# 2_PIS_TQ2416____V0_1.net
KiCad netlist of a schematic drawn in Altium Designer
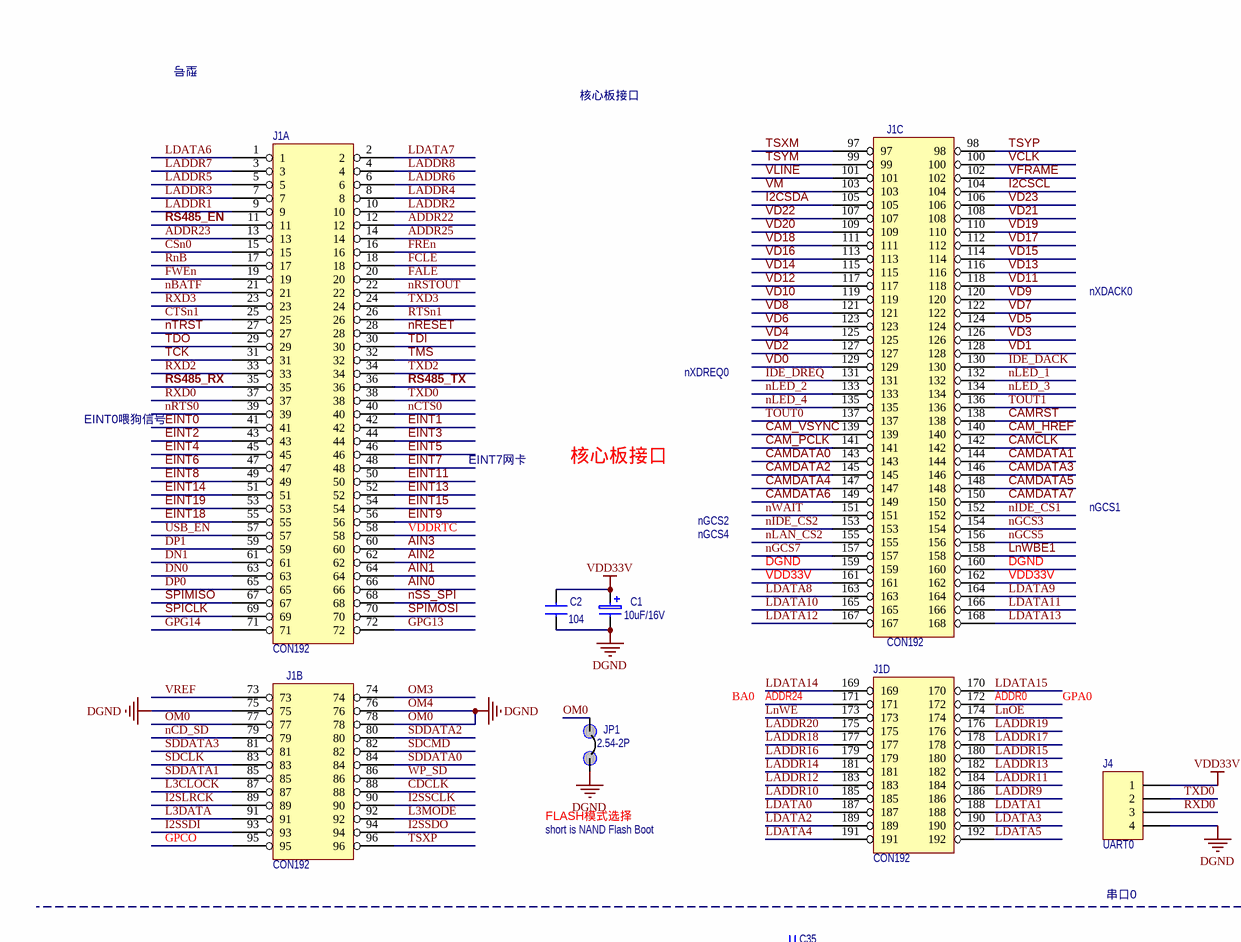
[diagram p0: 宁波2号线PIS_TQ2416底板_原理图_V0.1.schdoc, top left]
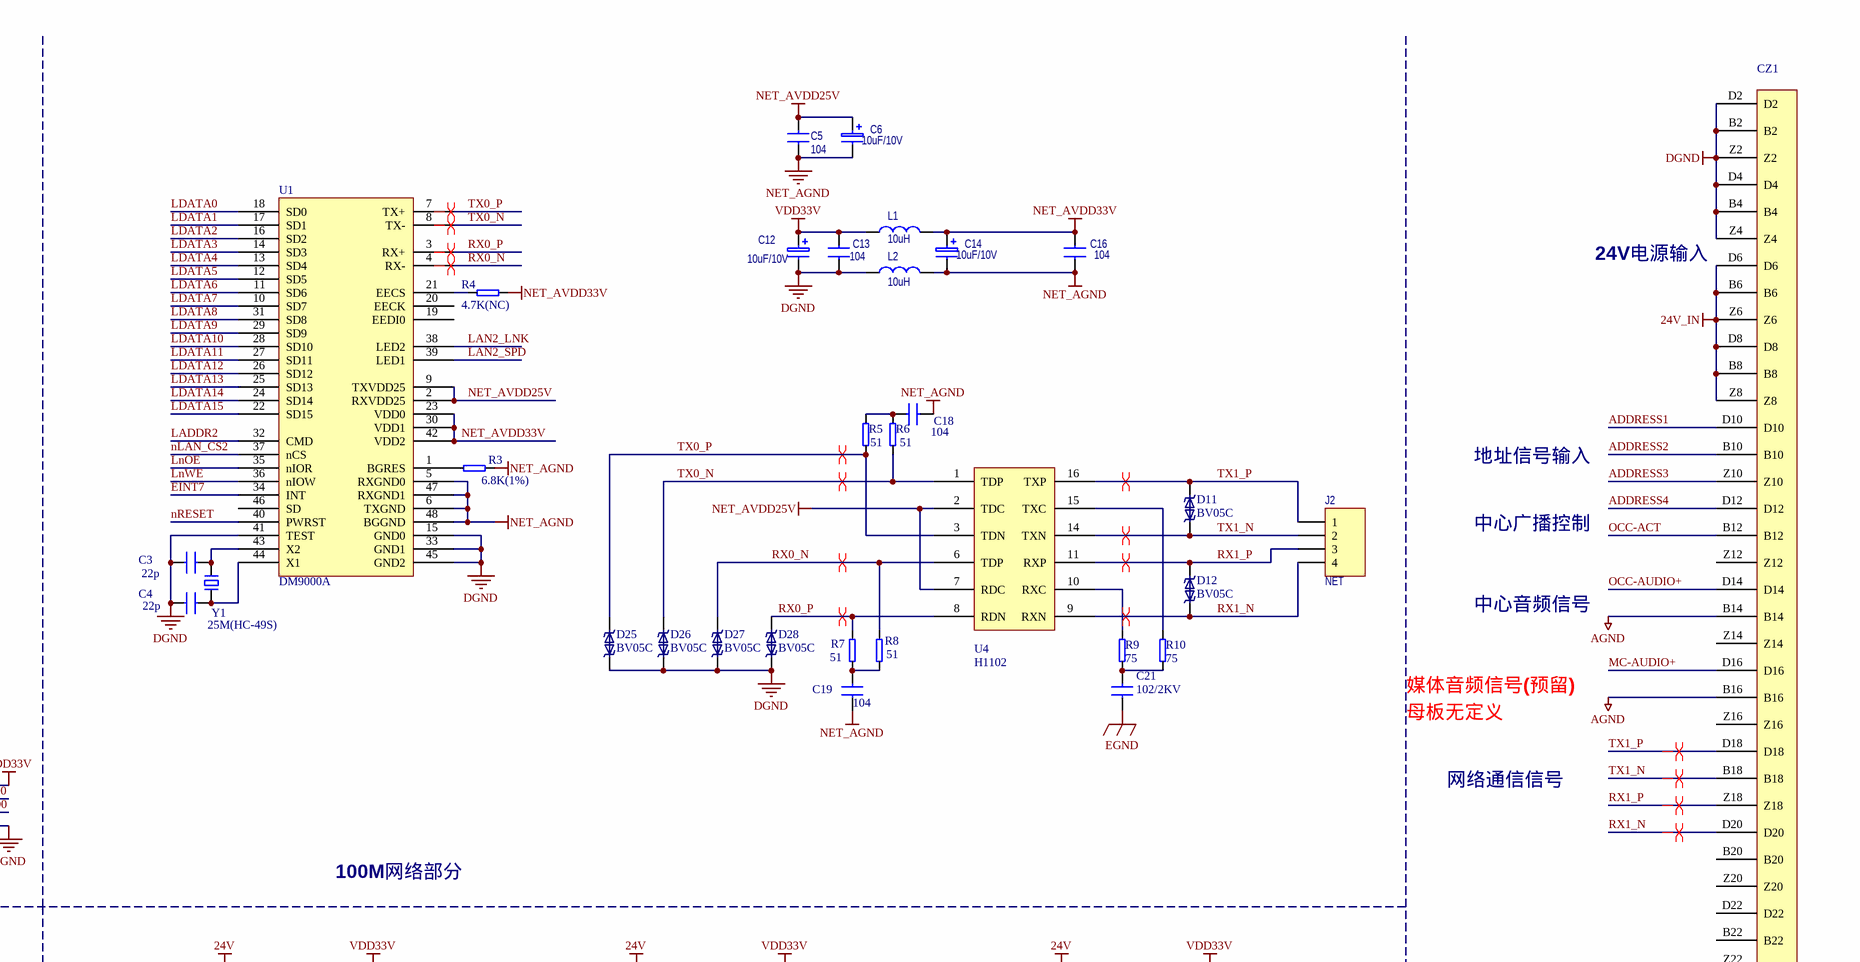
[diagram p1: 宁波2号线PIS_TQ2416底板_原理图_V0.1.schdoc, top right]
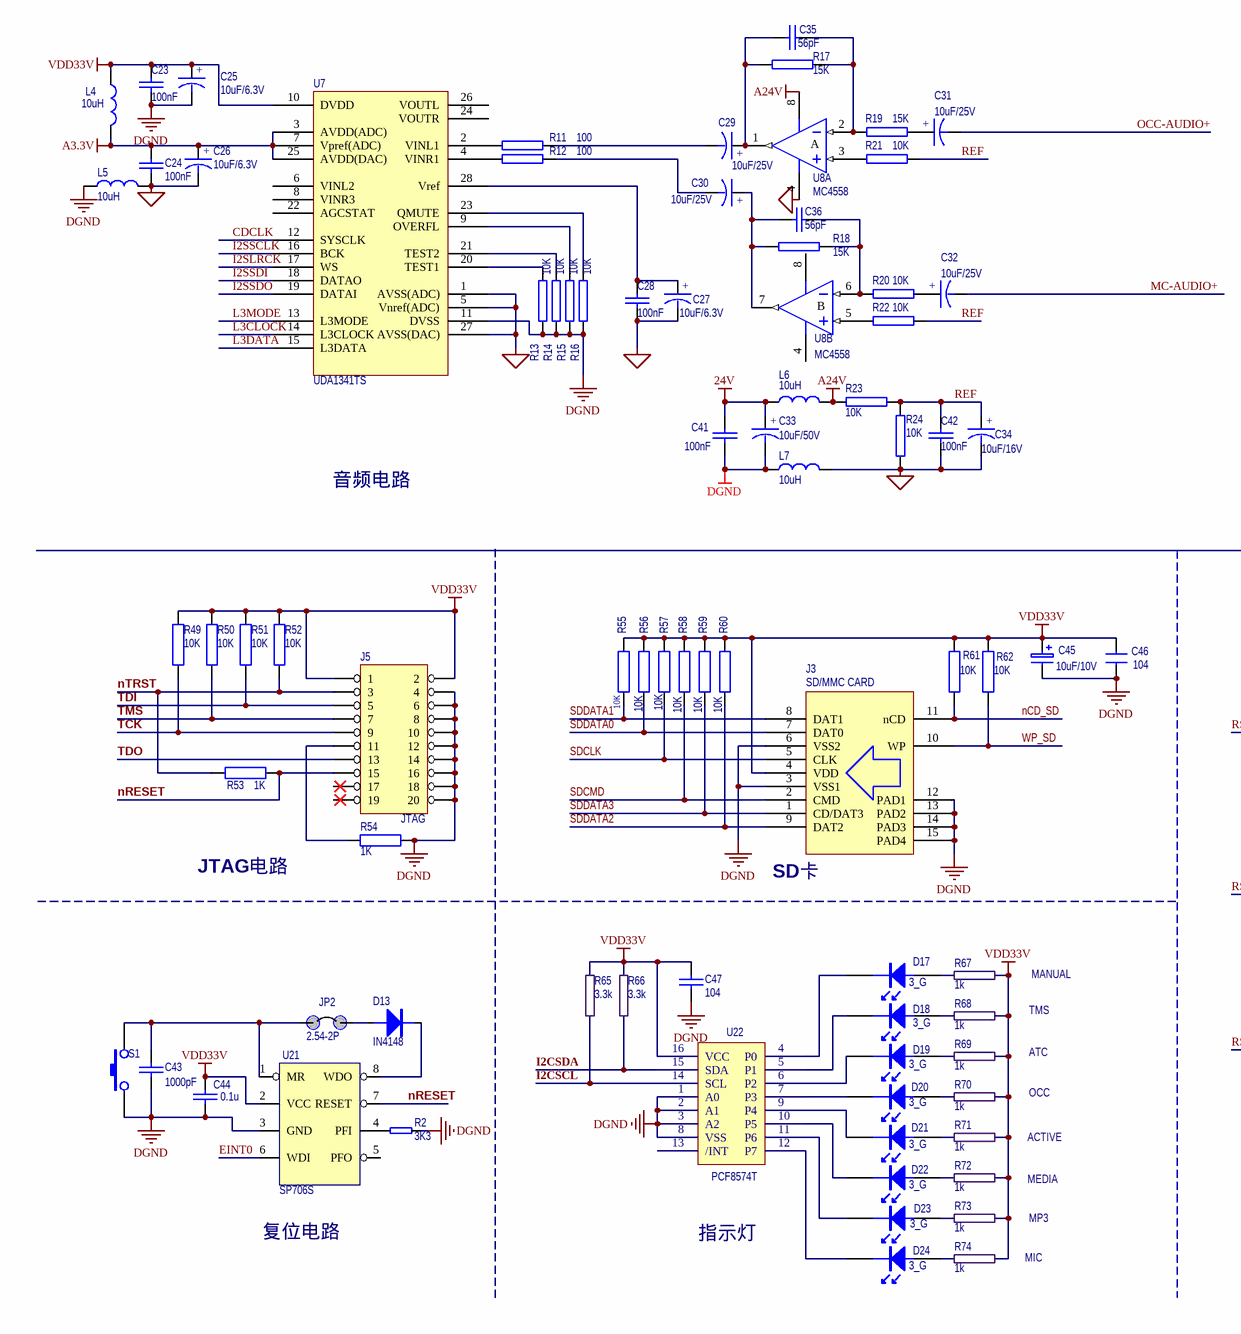
[diagram p2: 宁波2号线PIS_TQ2416底板_原理图_V0.1.schdoc, bottom left]
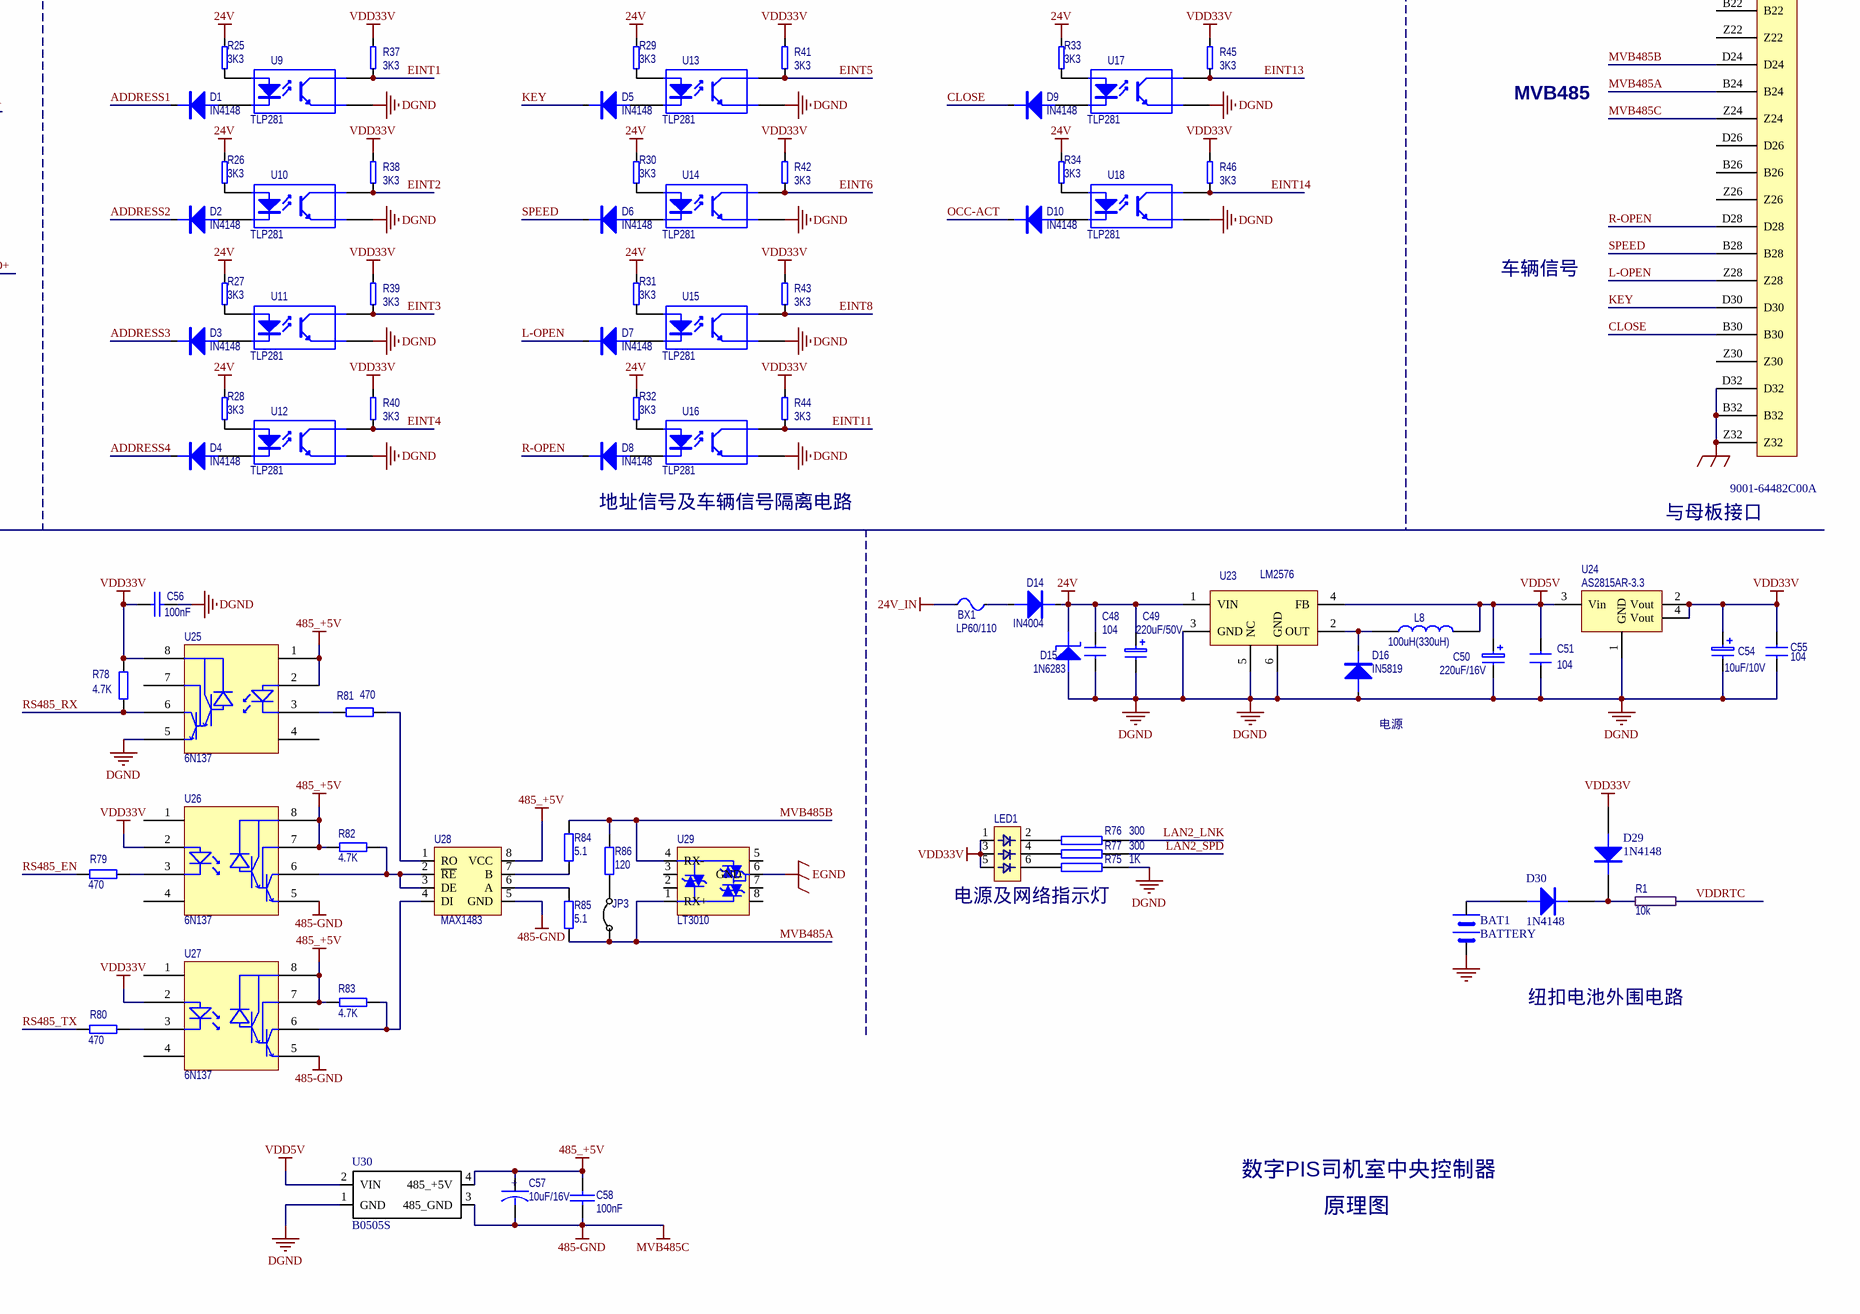
[diagram p3: 宁波2号线PIS_TQ2416底板_原理图_V0.1.schdoc, bottom right]

(export (version "E")
  (design (tool "Eeschema 10.0.6"))
  (components
    (comp (ref "BAT1") (value "BATTERY") (footprint "BAT600") (libsource (lib "*") (part "BATTERY")))
    (comp (ref "BX1") (value "LP60/110") (footprint "BX") (libsource (lib "*") (part "BX1")))
    (comp (ref "C1")
      (value "10uF/16V")
      (footprint "1206E")
      (description "Bi-Polar Capacitor")
      (fields (field (name "Comment") "10uF/10V"))
      (libsource (lib "*") (part "CAPBP2"))
    )
    (comp (ref "C2")
      (value "104")
      (footprint "0805C")
      (description "Capacitor")
      (libsource (lib "*") (part "CAP"))
    )
    (comp (ref "C3")
      (value "22p")
      (footprint "0805C")
      (description "Capacitor")
      (libsource (lib "*") (part "CAP"))
    )
    (comp (ref "C4")
      (value "22p")
      (footprint "0805C")
      (description "Capacitor")
      (libsource (lib "*") (part "CAP"))
    )
    (comp (ref "C5")
      (value "104")
      (footprint "0805C")
      (description "Capacitor")
      (libsource (lib "*") (part "CAP"))
    )
    (comp (ref "C6")
      (value "10uF/10V")
      (footprint "1206E")
      (description "Bi-Polar Capacitor")
      (libsource (lib "*") (part "CAPBP2"))
    )
    (comp (ref "C12")
      (value "10uF/10V")
      (footprint "1206E")
      (description "Bi-Polar Capacitor")
      (libsource (lib "*") (part "CAPBP2"))
    )
    (comp (ref "C13")
      (value "104")
      (footprint "0805C")
      (description "Capacitor")
      (libsource (lib "*") (part "CAP"))
    )
    (comp (ref "C14")
      (value "10uF/10V")
      (footprint "1206E")
      (description "Bi-Polar Capacitor")
      (libsource (lib "*") (part "CAPBP2"))
    )
    (comp (ref "C16")
      (value "104")
      (footprint "0805C")
      (description "Capacitor")
      (libsource (lib "*") (part "CAP"))
    )
    (comp (ref "C18")
      (value "104")
      (footprint "0805C")
      (description "Capacitor")
      (libsource (lib "*") (part "CAP"))
    )
    (comp (ref "C19")
      (value "104")
      (footprint "0805C")
      (description "Capacitor")
      (libsource (lib "*") (part "CAP"))
    )
    (comp (ref "C21")
      (value "102/2KV")
      (footprint "1206")
      (description "Capacitor")
      (libsource (lib "*") (part "CAP"))
    )
    (comp (ref "C23")
      (value "100nF")
      (footprint "0805C")
      (description "Capacitor")
      (libsource (lib "") (part "CAP_1"))
    )
    (comp (ref "C24")
      (value "100nF")
      (footprint "0805C")
      (description "Capacitor")
      (libsource (lib "") (part "CAP_1"))
    )
    (comp (ref "C25")
      (value "10uF/6.3V")
      (footprint "1206E")
      (description "Capacitor")
      (libsource (lib "*") (part "CAPACITOR POL"))
    )
    (comp (ref "C26")
      (value "10uF/6.3V")
      (footprint "1206E")
      (description "Capacitor")
      (libsource (lib "*") (part "CAPACITOR POL"))
    )
    (comp (ref "C27")
      (value "10uF/6.3V")
      (footprint "1206E")
      (description "Capacitor")
      (libsource (lib "*") (part "CAPACITOR POL"))
    )
    (comp (ref "C28")
      (value "100nF")
      (footprint "0805C")
      (description "Capacitor")
      (libsource (lib "") (part "CAP_1"))
    )
    (comp (ref "C29")
      (value "10uF/25V")
      (footprint "RB.1/.2")
      (description "Capacitor")
      (libsource (lib "*") (part "CAPACITOR POL"))
    )
    (comp (ref "C30")
      (value "10uF/25V")
      (footprint "RB.1/.2")
      (description "Capacitor")
      (libsource (lib "*") (part "CAPACITOR POL"))
    )
    (comp (ref "C31")
      (value "10uF/25V")
      (footprint "RB.1/.2")
      (description "Capacitor")
      (libsource (lib "*") (part "CAPACITOR POL"))
    )
    (comp (ref "C32")
      (value "10uF/25V")
      (footprint "RB.1/.2")
      (description "Capacitor")
      (libsource (lib "*") (part "CAPACITOR POL"))
    )
    (comp (ref "C33")
      (value "10uF/50V")
      (footprint "CAP-B")
      (description "Capacitor")
      (libsource (lib "*") (part "CAPACITOR POL"))
    )
    (comp (ref "C34")
      (value "10uF/16V")
      (footprint "CAP-B")
      (description "Capacitor")
      (libsource (lib "*") (part "CAPACITOR POL"))
    )
    (comp (ref "C35")
      (value "56pF")
      (footprint "0805C")
      (description "Capacitor")
      (libsource (lib "") (part "CAP_1"))
    )
    (comp (ref "C36")
      (value "56pF")
      (footprint "0805C")
      (description "Capacitor")
      (libsource (lib "") (part "CAP_1"))
    )
    (comp (ref "C41")
      (value "100nF")
      (footprint "0805C")
      (description "Capacitor")
      (libsource (lib "") (part "CAP_1"))
    )
    (comp (ref "C42")
      (value "100nF")
      (footprint "0805C")
      (description "Capacitor")
      (libsource (lib "") (part "CAP_1"))
    )
    (comp (ref "C43")
      (value "1000pF")
      (footprint "0805C")
      (description "Capacitor")
      (libsource (lib "") (part "CAP_2"))
    )
    (comp (ref "C44")
      (value "0.1u")
      (footprint "0805C")
      (description "Capacitor")
      (libsource (lib "") (part "CAP_2"))
    )
    (comp (ref "C45")
      (value "10uF/10V")
      (footprint "1206E")
      (description "Bi-Polar Capacitor")
      (libsource (lib "*") (part "CAPBP2"))
    )
    (comp (ref "C46")
      (value "104")
      (footprint "0805C")
      (description "Capacitor")
      (libsource (lib "*") (part "CAP"))
    )
    (comp (ref "C47")
      (value "104")
      (footprint "0805C")
      (description "Capacitor")
      (libsource (lib "") (part "CAP_3"))
    )
    (comp (ref "C48")
      (value "104")
      (footprint "0805C")
      (description "Capacitor")
      (libsource (lib "*") (part "CAP"))
    )
    (comp (ref "C49")
      (value "220uF/50V")
      (footprint "RB.2/.4")
      (description "Bi-Polar Capacitor")
      (libsource (lib "*") (part "CAPBP2"))
    )
    (comp (ref "C50")
      (value "220uF/16V")
      (footprint "RB.2/.4")
      (description "Bi-Polar Capacitor")
      (libsource (lib "*") (part "CAPBP2"))
    )
    (comp (ref "C51")
      (value "104")
      (footprint "0805C")
      (description "Capacitor")
      (libsource (lib "*") (part "CAP"))
    )
    (comp (ref "C54")
      (value "10uF/10V")
      (footprint "RB.2/.4")
      (description "Bi-Polar Capacitor")
      (fields (field (name "Comment") "220uF/16V"))
      (libsource (lib "*") (part "CAPBP2"))
    )
    (comp (ref "C55")
      (value "104")
      (footprint "0805C")
      (description "Capacitor")
      (libsource (lib "*") (part "CAP"))
    )
    (comp (ref "C56")
      (value "100nF")
      (footprint "0805C")
      (description "Capacitor")
      (libsource (lib "") (part "CAP_2"))
    )
    (comp (ref "C57")
      (value "10uF/16V")
      (footprint "1206E")
      (description "Capacitor")
      (libsource (lib "") (part "CAPACITOR POL_1"))
    )
    (comp (ref "C58")
      (value "100nF")
      (footprint "0805C")
      (description "Capacitor")
      (libsource (lib "") (part "CAP_1"))
    )
    (comp (ref "CZ1")
      (value "9001-64482C00A")
      (footprint "HARTING09061486901")
      (libsource (lib "*") (part "HARTING-48P"))
    )
    (comp (ref "D1")
      (value "IN4148")
      (footprint "SOD-323")
      (description "Diode")
      (libsource (lib "*") (part "DIODE"))
    )
    (comp (ref "D2")
      (value "IN4148")
      (footprint "SOD-323")
      (description "Diode")
      (libsource (lib "*") (part "DIODE"))
    )
    (comp (ref "D3")
      (value "IN4148")
      (footprint "SOD-323")
      (description "Diode")
      (libsource (lib "*") (part "DIODE"))
    )
    (comp (ref "D4")
      (value "IN4148")
      (footprint "SOD-323")
      (description "Diode")
      (libsource (lib "*") (part "DIODE"))
    )
    (comp (ref "D5")
      (value "IN4148")
      (footprint "SOD-323")
      (description "Diode")
      (libsource (lib "*") (part "DIODE"))
    )
    (comp (ref "D6")
      (value "IN4148")
      (footprint "SOD-323")
      (description "Diode")
      (libsource (lib "*") (part "DIODE"))
    )
    (comp (ref "D7")
      (value "IN4148")
      (footprint "SOD-323")
      (description "Diode")
      (libsource (lib "*") (part "DIODE"))
    )
    (comp (ref "D8")
      (value "IN4148")
      (footprint "SOD-323")
      (description "Diode")
      (libsource (lib "*") (part "DIODE"))
    )
    (comp (ref "D9")
      (value "IN4148")
      (footprint "SOD-323")
      (description "Diode")
      (libsource (lib "*") (part "DIODE"))
    )
    (comp (ref "D10")
      (value "IN4148")
      (footprint "SOD-323")
      (description "Diode")
      (libsource (lib "*") (part "DIODE"))
    )
    (comp (ref "D11") (value "BV05C") (footprint "SOD-323") (libsource (lib "Sch") (part "BV05C")))
    (comp (ref "D12") (value "BV05C") (footprint "SOD-323") (libsource (lib "Sch") (part "BV05C")))
    (comp (ref "D13")
      (value "IN4148")
      (footprint "0805AK")
      (description "Diode")
      (libsource (lib "*") (part "DIODE"))
    )
    (comp (ref "D14")
      (value "IN4004")
      (footprint "1206AK")
      (description "Diode")
      (libsource (lib "*") (part "DIODE"))
    )
    (comp (ref "D15")
      (value "1N6283")
      (footprint "DIODE0.5")
      (description "Zener Diode")
      (libsource (lib "*") (part "ZENER2"))
    )
    (comp (ref "D16")
      (value "IN5819")
      (footprint "1206AK")
      (description "Diode")
      (libsource (lib "*") (part "DIODE"))
    )
    (comp (ref "D17") (value "3_G") (footprint "LED-1") (libsource (lib "*") (part "LED")))
    (comp (ref "D18") (value "3_G") (footprint "LED-1") (libsource (lib "*") (part "LED")))
    (comp (ref "D19") (value "3_G") (footprint "LED-1") (libsource (lib "*") (part "LED")))
    (comp (ref "D20") (value "3_G") (footprint "LED-1") (libsource (lib "*") (part "LED")))
    (comp (ref "D21") (value "3_G") (footprint "LED-1") (libsource (lib "*") (part "LED")))
    (comp (ref "D22") (value "3_G") (footprint "LED-1") (libsource (lib "*") (part "LED")))
    (comp (ref "D23") (value "3_G") (footprint "LED-1") (libsource (lib "*") (part "LED")))
    (comp (ref "D24") (value "3_G") (footprint "LED-1") (libsource (lib "*") (part "LED")))
    (comp (ref "D25") (value "BV05C") (footprint "SOD-323") (libsource (lib "Sch") (part "BV05C")))
    (comp (ref "D26") (value "BV05C") (footprint "SOD-323") (libsource (lib "Sch") (part "BV05C")))
    (comp (ref "D27") (value "BV05C") (footprint "SOD-323") (libsource (lib "Sch") (part "BV05C")))
    (comp (ref "D28") (value "BV05C") (footprint "SOD-323") (libsource (lib "Sch") (part "BV05C")))
    (comp (ref "D29")
      (value "1N4148")
      (footprint "SOD-323")
      (description "Diode")
      (libsource (lib "") (part "DIODE_1"))
    )
    (comp (ref "D30")
      (value "1N4148")
      (footprint "SOD-323")
      (description "Diode")
      (libsource (lib "") (part "DIODE_1"))
    )
    (comp (ref "J1") (value "CON192") (footprint "CON192_2.0") (libsource (lib "*") (part "CON192")))
    (comp (ref "J2")
      (value "NET")
      (footprint "SIP-4")
      (description "Header, 4-Pin")
      (fields (field (name "PUBLISHER") "10K"))
      (libsource (lib "") (part "Header 4_1"))
    )
    (comp (ref "J3") (value "SD/MMC CARD") (footprint "SD_CARD(LONG)") (libsource (lib "*") (part "SD-CARD")))
    (comp (ref "J4")
      (value "UART0")
      (footprint "SIP-4")
      (description "Header, 4-Pin")
      (fields (field (name "PUBLISHER") "10K"))
      (libsource (lib "*") (part "Header 4"))
    )
    (comp (ref "J5") (value "JTAG") (footprint "DC3-20T") (libsource (lib "*") (part "HEADER 10X2")))
    (comp (ref "JP1") (value "2.54-2P") (footprint "JMP-2") (libsource (lib "*") (part "TX")))
    (comp (ref "JP2") (value "2.54-2P") (footprint "SIP-2") (libsource (lib "*") (part "TX")))
    (comp (ref "JP3") (value "~") (footprint "SIP-2") (libsource (lib "*") (part "J2")))
    (comp (ref "L1") (value "10uH") (footprint "1206") (libsource (lib "*") (part "INDUCTOR1")))
    (comp (ref "L2") (value "10uH") (footprint "1206") (libsource (lib "*") (part "INDUCTOR1")))
    (comp (ref "L4") (value "10uH") (footprint "1206") (libsource (lib "") (part "INDUCTOR1_2")))
    (comp (ref "L5") (value "10uH") (footprint "1206") (libsource (lib "*") (part "INDUCTOR1")))
    (comp (ref "L6") (value "10uH") (footprint "1206") (libsource (lib "*") (part "INDUCTOR1")))
    (comp (ref "L7") (value "10uH") (footprint "1206") (libsource (lib "*") (part "INDUCTOR1")))
    (comp (ref "L8") (value "100uH(330uH)") (footprint "DG300") (libsource (lib "") (part "INDUCTOR1_1")))
    (comp (ref "LED1") (value "~") (footprint "LED-3") (libsource (lib "*") (part "3-LED")))
    (comp (ref "R1") (value "10k") (footprint "0805R") (libsource (lib "") (part "R_1")))
    (comp (ref "R2") (value "3K3") (footprint "0805R") (libsource (lib "*") (part "R")))
    (comp (ref "R3") (value "6.8K(1%)") (footprint "0805R") (libsource (lib "") (part "R_2")))
    (comp (ref "R4") (value "4.7K(NC)") (footprint "0805R") (libsource (lib "") (part "R_2")))
    (comp (ref "R5") (value "51") (footprint "0805R") (libsource (lib "") (part "R_2")))
    (comp (ref "R6") (value "51") (footprint "0805R") (libsource (lib "") (part "R_2")))
    (comp (ref "R7") (value "51") (footprint "0805R") (libsource (lib "") (part "R_2")))
    (comp (ref "R8") (value "51") (footprint "0805R") (libsource (lib "") (part "R_2")))
    (comp (ref "R9") (value "75") (footprint "0805R") (libsource (lib "") (part "R_2")))
    (comp (ref "R10") (value "75") (footprint "0805R") (libsource (lib "") (part "R_2")))
    (comp (ref "R11") (value "100") (footprint "0805R") (libsource (lib "") (part "RES2_4")))
    (comp (ref "R12") (value "100") (footprint "0805R") (libsource (lib "") (part "RES2_4")))
    (comp (ref "R13") (value "10K") (footprint "0805R") (libsource (lib "") (part "RES2_4")))
    (comp (ref "R14") (value "10K") (footprint "0805R") (libsource (lib "") (part "RES2_4")))
    (comp (ref "R15") (value "10K") (footprint "0805R") (libsource (lib "") (part "RES2_4")))
    (comp (ref "R16") (value "10K") (footprint "0805R") (libsource (lib "") (part "RES2_4")))
    (comp (ref "R17") (value "15K") (footprint "0805R") (libsource (lib "") (part "RES2_4")))
    (comp (ref "R18") (value "15K") (footprint "0805R") (libsource (lib "") (part "RES2_4")))
    (comp (ref "R19") (value "15K") (footprint "0805R") (libsource (lib "") (part "RES2_4")))
    (comp (ref "R20") (value "10K") (footprint "0805R") (libsource (lib "") (part "RES2_4")))
    (comp (ref "R21") (value "10K") (footprint "0805R") (libsource (lib "") (part "RES2_4")))
    (comp (ref "R22") (value "10K") (footprint "0805R") (libsource (lib "") (part "RES2_4")))
    (comp (ref "R23") (value "10K") (footprint "0805R") (libsource (lib "") (part "RES2_4")))
    (comp (ref "R24") (value "10K") (footprint "0805R") (libsource (lib "") (part "RES2_4")))
    (comp (ref "R25") (value "3K3") (footprint "0805R") (libsource (lib "*") (part "R")))
    (comp (ref "R26") (value "3K3") (footprint "0805R") (libsource (lib "*") (part "R")))
    (comp (ref "R27") (value "3K3") (footprint "0805R") (libsource (lib "*") (part "R")))
    (comp (ref "R28") (value "3K3") (footprint "0805R") (libsource (lib "*") (part "R")))
    (comp (ref "R29") (value "3K3") (footprint "0805R") (libsource (lib "*") (part "R")))
    (comp (ref "R30") (value "3K3") (footprint "0805R") (libsource (lib "*") (part "R")))
    (comp (ref "R31") (value "3K3") (footprint "0805R") (libsource (lib "*") (part "R")))
    (comp (ref "R32") (value "3K3") (footprint "0805R") (libsource (lib "*") (part "R")))
    (comp (ref "R33") (value "3K3") (footprint "0805R") (libsource (lib "*") (part "R")))
    (comp (ref "R34") (value "3K3") (footprint "0805R") (libsource (lib "*") (part "R")))
    (comp (ref "R37") (value "3K3") (footprint "0805R") (libsource (lib "*") (part "R")))
    (comp (ref "R38") (value "3K3") (footprint "0805R") (libsource (lib "*") (part "R")))
    (comp (ref "R39") (value "3K3") (footprint "0805R") (libsource (lib "*") (part "R")))
    (comp (ref "R40") (value "3K3") (footprint "0805R") (libsource (lib "*") (part "R")))
    (comp (ref "R41") (value "3K3") (footprint "0805R") (libsource (lib "*") (part "R")))
    (comp (ref "R42") (value "3K3") (footprint "0805R") (libsource (lib "*") (part "R")))
    (comp (ref "R43") (value "3K3") (footprint "0805R") (libsource (lib "*") (part "R")))
    (comp (ref "R44") (value "3K3") (footprint "0805R") (libsource (lib "*") (part "R")))
    (comp (ref "R45") (value "3K3") (footprint "0805R") (libsource (lib "*") (part "R")))
    (comp (ref "R46") (value "3K3") (footprint "0805R") (libsource (lib "*") (part "R")))
    (comp (ref "R49")
      (value "10K")
      (footprint "0805R")
      (description "Resistor")
      (libsource (lib "") (part "RES2_1"))
    )
    (comp (ref "R50")
      (value "10K")
      (footprint "0805R")
      (description "Resistor")
      (libsource (lib "") (part "RES2_1"))
    )
    (comp (ref "R51")
      (value "10K")
      (footprint "0805R")
      (description "Resistor")
      (libsource (lib "") (part "RES2_1"))
    )
    (comp (ref "R52")
      (value "10K")
      (footprint "0805R")
      (description "Resistor")
      (libsource (lib "") (part "RES2_1"))
    )
    (comp (ref "R53")
      (value "1K")
      (footprint "0805R")
      (description "Resistor")
      (libsource (lib "") (part "RES2_3"))
    )
    (comp (ref "R54")
      (value "1K")
      (footprint "0805R")
      (description "Resistor")
      (libsource (lib "") (part "RES2_3"))
    )
    (comp (ref "R55")
      (value "10K")
      (footprint "0805R")
      (description "Resistor")
      (libsource (lib "") (part "RES2_1"))
    )
    (comp (ref "R56")
      (value "10K")
      (footprint "0805R")
      (description "Resistor")
      (libsource (lib "") (part "RES2_1"))
    )
    (comp (ref "R57")
      (value "10K")
      (footprint "0805R")
      (description "Resistor")
      (libsource (lib "") (part "RES2_1"))
    )
    (comp (ref "R58")
      (value "10K")
      (footprint "0805R")
      (description "Resistor")
      (libsource (lib "") (part "RES2_1"))
    )
    (comp (ref "R59")
      (value "10K")
      (footprint "0805R")
      (description "Resistor")
      (libsource (lib "") (part "RES2_1"))
    )
    (comp (ref "R60")
      (value "10K")
      (footprint "0805R")
      (description "Resistor")
      (libsource (lib "") (part "RES2_1"))
    )
    (comp (ref "R61")
      (value "10K")
      (footprint "0805R")
      (description "Resistor")
      (libsource (lib "") (part "RES2_1"))
    )
    (comp (ref "R62")
      (value "10K")
      (footprint "0805R")
      (description "Resistor")
      (libsource (lib "") (part "RES2_1"))
    )
    (comp (ref "R65") (value "3.3k") (footprint "0805R") (libsource (lib "") (part "R_1")))
    (comp (ref "R66") (value "3.3k") (footprint "0805R") (libsource (lib "") (part "R_1")))
    (comp (ref "R67") (value "1k") (footprint "0805R") (libsource (lib "") (part "R_1")))
    (comp (ref "R68") (value "1k") (footprint "0805R") (libsource (lib "") (part "R_1")))
    (comp (ref "R69") (value "1k") (footprint "0805R") (libsource (lib "") (part "R_1")))
    (comp (ref "R70") (value "1k") (footprint "0805R") (libsource (lib "") (part "R_1")))
    (comp (ref "R71") (value "1k") (footprint "0805R") (libsource (lib "") (part "R_1")))
    (comp (ref "R72") (value "1k") (footprint "0805R") (libsource (lib "") (part "R_1")))
    (comp (ref "R73") (value "1k") (footprint "0805R") (libsource (lib "") (part "R_1")))
    (comp (ref "R74") (value "1k") (footprint "0805R") (libsource (lib "") (part "R_1")))
    (comp (ref "R75") (value "1K") (footprint "0805R") (libsource (lib "") (part "RES2_2")))
    (comp (ref "R76") (value "300") (footprint "0805R") (libsource (lib "") (part "RES2_2")))
    (comp (ref "R77") (value "300") (footprint "0805R") (libsource (lib "") (part "RES2_2")))
    (comp (ref "R78") (value "4.7K") (footprint "0805R") (libsource (lib "*") (part "RES2")))
    (comp (ref "R79") (value "470") (footprint "0805R") (libsource (lib "*") (part "RES2")))
    (comp (ref "R80") (value "470") (footprint "0805R") (libsource (lib "*") (part "RES2")))
    (comp (ref "R81") (value "470") (footprint "0805R") (libsource (lib "*") (part "RES2")))
    (comp (ref "R82") (value "4.7K") (footprint "0805R") (libsource (lib "*") (part "RES2")))
    (comp (ref "R83") (value "4.7K") (footprint "0805R") (libsource (lib "*") (part "RES2")))
    (comp (ref "R84") (value "5.1") (footprint "0805R") (libsource (lib "*") (part "RES2")))
    (comp (ref "R85") (value "5.1") (footprint "0805R") (libsource (lib "*") (part "RES2")))
    (comp (ref "R86") (value "120") (footprint "0805R") (libsource (lib "*") (part "RES2")))
    (comp (ref "S1") (value "~") (footprint "KEY-6A") (libsource (lib "*") (part "SW-PB")))
    (comp (ref "U1") (value "DM9000A") (footprint "LQFP-48") (libsource (lib "*") (part "DM9000A")))
    (comp (ref "U4") (value "H1102") (footprint "SOP-16(Wide)") (libsource (lib "*") (part "H1102")))
    (comp (ref "U7") (value "UDA1341TS") (footprint "TSSOP-28") (libsource (lib "*") (part "UDA1341TS")))
    (comp (ref "U8")
      (value "MC4558")
      (footprint "SOP-8")
      (description "Dual Rail-to-Rail Operational Amplifier")
      (fields (field (name "PUBLISHER") "10K"))
      (libsource (lib "*") (part "OP295GS"))
    )
    (comp (ref "U9")
      (value "TLP281")
      (footprint "SOP-4")
      (description "Optoisolator")
      (libsource (lib "*") (part "OPTOISO1"))
    )
    (comp (ref "U10")
      (value "TLP281")
      (footprint "SOP-4")
      (description "Optoisolator")
      (libsource (lib "*") (part "OPTOISO1"))
    )
    (comp (ref "U11")
      (value "TLP281")
      (footprint "SOP-4")
      (description "Optoisolator")
      (libsource (lib "*") (part "OPTOISO1"))
    )
    (comp (ref "U12")
      (value "TLP281")
      (footprint "SOP-4")
      (description "Optoisolator")
      (libsource (lib "*") (part "OPTOISO1"))
    )
    (comp (ref "U13")
      (value "TLP281")
      (footprint "SOP-4")
      (description "Optoisolator")
      (libsource (lib "*") (part "OPTOISO1"))
    )
    (comp (ref "U14")
      (value "TLP281")
      (footprint "SOP-4")
      (description "Optoisolator")
      (libsource (lib "*") (part "OPTOISO1"))
    )
    (comp (ref "U15")
      (value "TLP281")
      (footprint "SOP-4")
      (description "Optoisolator")
      (libsource (lib "*") (part "OPTOISO1"))
    )
    (comp (ref "U16")
      (value "TLP281")
      (footprint "SOP-4")
      (description "Optoisolator")
      (libsource (lib "*") (part "OPTOISO1"))
    )
    (comp (ref "U17")
      (value "TLP281")
      (footprint "SOP-4")
      (description "Optoisolator")
      (libsource (lib "*") (part "OPTOISO1"))
    )
    (comp (ref "U18")
      (value "TLP281")
      (footprint "SOP-4")
      (description "Optoisolator")
      (libsource (lib "*") (part "OPTOISO1"))
    )
    (comp (ref "U21") (value "SP706S") (footprint "SOP-8") (libsource (lib "*") (part "MAX706R")))
    (comp (ref "U22") (value "PCF8574T") (footprint "SOP-16") (libsource (lib "*") (part "PCF8574")))
    (comp (ref "U23") (value "LM2576") (footprint "LM2576") (libsource (lib "*") (part "LM2576")))
    (comp (ref "U24") (value "AS2815AR-3.3") (footprint "TO-252") (libsource (lib "*") (part "LT1085")))
    (comp (ref "U25") (value "6N137") (footprint "SOP-8-2.54") (libsource (lib "") (part "6N138_1")))
    (comp (ref "U26") (value "6N137") (footprint "SOP-8-2.54") (libsource (lib "*") (part "6N138")))
    (comp (ref "U27") (value "6N137") (footprint "SOP-8-2.54") (libsource (lib "*") (part "6N138")))
    (comp (ref "U28") (value "MAX1483") (footprint "SOP-8") (libsource (lib "*") (part "MAX1483")))
    (comp (ref "U29") (value "LT3010") (footprint "SOP-8") (libsource (lib "*") (part "LT3010")))
    (comp (ref "U30") (value "B0505S") (footprint "B0505S") (libsource (lib "Sch") (part "B0505S")))
    (comp (ref "Y1") (value "25M(HC-49S)") (footprint "CRYSTAL") (libsource (lib "*") (part "JT")))
  )
  (nets
    (net (code "1") (name "/ADDR22") (class "Default")
      (node (ref "J1") (pin "12") (pinfunction "12_12") (pintype "passive"))
    )
    (net (code "2") (name "/ADDR23") (class "Default")
      (node (ref "J1") (pin "13") (pinfunction "13_13") (pintype "passive"))
    )
    (net (code "3") (name "/ADDR25") (class "Default")
      (node (ref "J1") (pin "14") (pinfunction "14_14") (pintype "passive"))
    )
    (net (code "4") (name "/ADDRESS1") (class "Default")
      (node (ref "CZ1") (pin "D10") (pinfunction "D10_D10") (pintype "passive"))
      (node (ref "D1") (pin "K") (pinfunction "K_K") (pintype "passive"))
    )
    (net (code "5") (name "/ADDRESS2") (class "Default")
      (node (ref "CZ1") (pin "B10") (pinfunction "B10_B10") (pintype "passive"))
      (node (ref "D2") (pin "K") (pinfunction "K_K") (pintype "passive"))
    )
    (net (code "6") (name "/ADDRESS3") (class "Default")
      (node (ref "CZ1") (pin "Z10") (pinfunction "Z10_Z10") (pintype "passive"))
      (node (ref "D3") (pin "K") (pinfunction "K_K") (pintype "passive"))
    )
    (net (code "7") (name "/ADDRESS4") (class "Default")
      (node (ref "CZ1") (pin "D12") (pinfunction "D12_D12") (pintype "passive"))
      (node (ref "D4") (pin "K") (pinfunction "K_K") (pintype "passive"))
    )
    (net (code "8") (name "/AIN0") (class "Default")
      (node (ref "J1") (pin "66") (pinfunction "66_66") (pintype "passive"))
    )
    (net (code "9") (name "/AIN1") (class "Default")
      (node (ref "J1") (pin "64") (pinfunction "64_64") (pintype "passive"))
    )
    (net (code "10") (name "/AIN2") (class "Default")
      (node (ref "J1") (pin "62") (pinfunction "62_62") (pintype "passive"))
    )
    (net (code "11") (name "/AIN3") (class "Default")
      (node (ref "J1") (pin "60") (pinfunction "60_60") (pintype "passive"))
    )
    (net (code "12") (name "/CAMCLK") (class "Default")
      (node (ref "J1") (pin "142") (pinfunction "142_142") (pintype "passive"))
    )
    (net (code "13") (name "/CAMDATA0") (class "Default")
      (node (ref "J1") (pin "143") (pinfunction "143_143") (pintype "passive"))
    )
    (net (code "14") (name "/CAMDATA1") (class "Default")
      (node (ref "J1") (pin "144") (pinfunction "144_144") (pintype "passive"))
    )
    (net (code "15") (name "/CAMDATA2") (class "Default")
      (node (ref "J1") (pin "145") (pinfunction "145_145") (pintype "passive"))
    )
    (net (code "16") (name "/CAMDATA3") (class "Default")
      (node (ref "J1") (pin "146") (pinfunction "146_146") (pintype "passive"))
    )
    (net (code "17") (name "/CAMDATA4") (class "Default")
      (node (ref "J1") (pin "147") (pinfunction "147_147") (pintype "passive"))
    )
    (net (code "18") (name "/CAMDATA5") (class "Default")
      (node (ref "J1") (pin "148") (pinfunction "148_148") (pintype "passive"))
    )
    (net (code "19") (name "/CAMDATA6") (class "Default")
      (node (ref "J1") (pin "149") (pinfunction "149_149") (pintype "passive"))
    )
    (net (code "20") (name "/CAMDATA7") (class "Default")
      (node (ref "J1") (pin "150") (pinfunction "150_150") (pintype "passive"))
    )
    (net (code "21") (name "/CAMRST") (class "Default")
      (node (ref "J1") (pin "138") (pinfunction "138_138") (pintype "passive"))
    )
    (net (code "22") (name "/CAM_HREF") (class "Default")
      (node (ref "J1") (pin "140") (pinfunction "140_140") (pintype "passive"))
    )
    (net (code "23") (name "/CAM_PCLK") (class "Default")
      (node (ref "J1") (pin "141") (pinfunction "141_141") (pintype "passive"))
    )
    (net (code "24") (name "/CAM_VSYNC") (class "Default")
      (node (ref "J1") (pin "139") (pinfunction "139_139") (pintype "passive"))
    )
    (net (code "25") (name "/CDCLK") (class "Default")
      (node (ref "J1") (pin "88") (pinfunction "88_88") (pintype "passive"))
      (node (ref "U7") (pin "12") (pinfunction "SYSCLK_12") (pintype "passive"))
    )
    (net (code "26") (name "/CLOSE") (class "Default")
      (node (ref "CZ1") (pin "B30") (pinfunction "B30_B30") (pintype "passive"))
      (node (ref "D9") (pin "K") (pinfunction "K_K") (pintype "passive"))
    )
    (net (code "27") (name "/CSn0") (class "Default")
      (node (ref "J1") (pin "15") (pinfunction "15_15") (pintype "passive"))
    )
    (net (code "28") (name "/CTSn1") (class "Default")
      (node (ref "J1") (pin "25") (pinfunction "25_25") (pintype "passive"))
    )
    (net (code "29") (name "/DN0") (class "Default")
      (node (ref "J1") (pin "63") (pinfunction "63_63") (pintype "passive"))
    )
    (net (code "30") (name "/DN1") (class "Default")
      (node (ref "J1") (pin "61") (pinfunction "61_61") (pintype "passive"))
    )
    (net (code "31") (name "/DP0") (class "Default")
      (node (ref "J1") (pin "65") (pinfunction "65_65") (pintype "passive"))
    )
    (net (code "32") (name "/DP1") (class "Default")
      (node (ref "J1") (pin "59") (pinfunction "59_59") (pintype "passive"))
    )
    (net (code "33") (name "/EINT0") (class "Default")
      (node (ref "J1") (pin "41") (pinfunction "41_41") (pintype "passive"))
      (node (ref "U21") (pin "6") (pinfunction "WDI_6") (pintype "passive"))
    )
    (net (code "34") (name "/EINT1") (class "Default")
      (node (ref "J1") (pin "42") (pinfunction "42_42") (pintype "passive"))
      (node (ref "R37") (pin "1") (pinfunction "1_1") (pintype "passive"))
      (node (ref "U9") (pin "4") (pinfunction "C_4") (pintype "passive"))
    )
    (net (code "35") (name "/EINT2") (class "Default")
      (node (ref "J1") (pin "43") (pinfunction "43_43") (pintype "passive"))
      (node (ref "R38") (pin "1") (pinfunction "1_1") (pintype "passive"))
      (node (ref "U10") (pin "4") (pinfunction "C_4") (pintype "passive"))
    )
    (net (code "36") (name "/EINT3") (class "Default")
      (node (ref "J1") (pin "44") (pinfunction "44_44") (pintype "passive"))
      (node (ref "R39") (pin "1") (pinfunction "1_1") (pintype "passive"))
      (node (ref "U11") (pin "4") (pinfunction "C_4") (pintype "passive"))
    )
    (net (code "37") (name "/EINT4") (class "Default")
      (node (ref "J1") (pin "45") (pinfunction "45_45") (pintype "passive"))
      (node (ref "R40") (pin "1") (pinfunction "1_1") (pintype "passive"))
      (node (ref "U12") (pin "4") (pinfunction "C_4") (pintype "passive"))
    )
    (net (code "38") (name "/EINT5") (class "Default")
      (node (ref "J1") (pin "46") (pinfunction "46_46") (pintype "passive"))
      (node (ref "R41") (pin "1") (pinfunction "1_1") (pintype "passive"))
      (node (ref "U13") (pin "4") (pinfunction "C_4") (pintype "passive"))
    )
    (net (code "39") (name "/EINT6") (class "Default")
      (node (ref "J1") (pin "47") (pinfunction "47_47") (pintype "passive"))
      (node (ref "R42") (pin "1") (pinfunction "1_1") (pintype "passive"))
      (node (ref "U14") (pin "4") (pinfunction "C_4") (pintype "passive"))
    )
    (net (code "40") (name "/EINT7") (class "Default")
      (node (ref "J1") (pin "48") (pinfunction "48_48") (pintype "passive"))
      (node (ref "U1") (pin "34") (pinfunction "INT_34") (pintype "passive"))
    )
    (net (code "41") (name "/EINT8") (class "Default")
      (node (ref "J1") (pin "49") (pinfunction "49_49") (pintype "passive"))
      (node (ref "R43") (pin "1") (pinfunction "1_1") (pintype "passive"))
      (node (ref "U15") (pin "4") (pinfunction "C_4") (pintype "passive"))
    )
    (net (code "42") (name "/EINT9") (class "Default")
      (node (ref "J1") (pin "56") (pinfunction "56_56") (pintype "passive"))
    )
    (net (code "43") (name "/EINT11") (class "Default")
      (node (ref "J1") (pin "50") (pinfunction "50_50") (pintype "passive"))
      (node (ref "R44") (pin "1") (pinfunction "1_1") (pintype "passive"))
      (node (ref "U16") (pin "4") (pinfunction "C_4") (pintype "passive"))
    )
    (net (code "44") (name "/EINT13") (class "Default")
      (node (ref "J1") (pin "52") (pinfunction "52_52") (pintype "passive"))
      (node (ref "R45") (pin "1") (pinfunction "1_1") (pintype "passive"))
      (node (ref "U17") (pin "4") (pinfunction "C_4") (pintype "passive"))
    )
    (net (code "45") (name "/EINT14") (class "Default")
      (node (ref "J1") (pin "51") (pinfunction "51_51") (pintype "passive"))
      (node (ref "R46") (pin "1") (pinfunction "1_1") (pintype "passive"))
      (node (ref "U18") (pin "4") (pinfunction "C_4") (pintype "passive"))
    )
    (net (code "46") (name "/EINT15") (class "Default")
      (node (ref "J1") (pin "54") (pinfunction "54_54") (pintype "passive"))
    )
    (net (code "47") (name "/EINT18") (class "Default")
      (node (ref "J1") (pin "55") (pinfunction "55_55") (pintype "passive"))
    )
    (net (code "48") (name "/EINT19") (class "Default")
      (node (ref "J1") (pin "53") (pinfunction "53_53") (pintype "passive"))
    )
    (net (code "49") (name "/FALE") (class "Default")
      (node (ref "J1") (pin "20") (pinfunction "20_20") (pintype "passive"))
    )
    (net (code "50") (name "/FCLE") (class "Default")
      (node (ref "J1") (pin "18") (pinfunction "18_18") (pintype "passive"))
    )
    (net (code "51") (name "/FREn") (class "Default")
      (node (ref "J1") (pin "16") (pinfunction "16_16") (pintype "passive"))
    )
    (net (code "52") (name "/FWEn") (class "Default")
      (node (ref "J1") (pin "19") (pinfunction "19_19") (pintype "passive"))
    )
    (net (code "53") (name "/GPCO") (class "Default")
      (node (ref "J1") (pin "95") (pinfunction "95_95") (pintype "passive"))
    )
    (net (code "54") (name "/GPG13") (class "Default")
      (node (ref "J1") (pin "72") (pinfunction "72_72") (pintype "passive"))
    )
    (net (code "55") (name "/GPG14") (class "Default")
      (node (ref "J1") (pin "71") (pinfunction "71_71") (pintype "passive"))
    )
    (net (code "56") (name "/I2CSCL") (class "Default")
      (node (ref "J1") (pin "104") (pinfunction "104_104") (pintype "passive"))
      (node (ref "R65") (pin "2") (pintype "passive"))
      (node (ref "U22") (pin "14") (pinfunction "SCL_14") (pintype "passive"))
    )
    (net (code "57") (name "/I2CSDA") (class "Default")
      (node (ref "J1") (pin "105") (pinfunction "105_105") (pintype "passive"))
      (node (ref "R66") (pin "2") (pintype "passive"))
      (node (ref "U22") (pin "15") (pinfunction "SDA_15") (pintype "passive"))
    )
    (net (code "58") (name "/I2SLRCK") (class "Default")
      (node (ref "J1") (pin "89") (pinfunction "89_89") (pintype "passive"))
      (node (ref "U7") (pin "17") (pinfunction "WS_17") (pintype "passive"))
    )
    (net (code "59") (name "/I2SSCLK") (class "Default")
      (node (ref "J1") (pin "90") (pinfunction "90_90") (pintype "passive"))
      (node (ref "U7") (pin "16") (pinfunction "BCK_16") (pintype "passive"))
    )
    (net (code "60") (name "/I2SSDI") (class "Default")
      (node (ref "J1") (pin "93") (pinfunction "93_93") (pintype "passive"))
      (node (ref "U7") (pin "18") (pinfunction "DATAO_18") (pintype "passive"))
    )
    (net (code "61") (name "/I2SSDO") (class "Default")
      (node (ref "J1") (pin "94") (pinfunction "94_94") (pintype "passive"))
      (node (ref "U7") (pin "19") (pinfunction "DATAI_19") (pintype "passive"))
    )
    (net (code "62") (name "/IDE_DACK") (class "Default")
      (node (ref "J1") (pin "130") (pinfunction "130_130") (pintype "passive"))
    )
    (net (code "63") (name "/IDE_DREQ") (class "Default")
      (node (ref "J1") (pin "131") (pinfunction "131_131") (pintype "passive"))
    )
    (net (code "64") (name "/KEY") (class "Default")
      (node (ref "CZ1") (pin "D30") (pinfunction "D30_D30") (pintype "passive"))
      (node (ref "D5") (pin "K") (pinfunction "K_K") (pintype "passive"))
    )
    (net (code "65") (name "/L-OPEN") (class "Default")
      (node (ref "CZ1") (pin "Z28") (pinfunction "Z28_Z28") (pintype "passive"))
      (node (ref "D7") (pin "K") (pinfunction "K_K") (pintype "passive"))
    )
    (net (code "66") (name "/L3CLOCK") (class "Default")
      (node (ref "J1") (pin "87") (pinfunction "87_87") (pintype "passive"))
      (node (ref "U7") (pin "14") (pinfunction "L3CLOCK_14") (pintype "passive"))
    )
    (net (code "67") (name "/L3DATA") (class "Default")
      (node (ref "J1") (pin "91") (pinfunction "91_91") (pintype "passive"))
      (node (ref "U7") (pin "15") (pinfunction "L3DATA_15") (pintype "passive"))
    )
    (net (code "68") (name "/L3MODE") (class "Default")
      (node (ref "J1") (pin "92") (pinfunction "92_92") (pintype "passive"))
      (node (ref "U7") (pin "13") (pinfunction "L3MODE_13") (pintype "passive"))
    )
    (net (code "69") (name "/LADDR1") (class "Default")
      (node (ref "J1") (pin "9") (pinfunction "9_9") (pintype "passive"))
    )
    (net (code "70") (name "/LADDR2") (class "Default")
      (node (ref "J1") (pin "10") (pinfunction "10_10") (pintype "passive"))
      (node (ref "U1") (pin "32") (pinfunction "CMD_32") (pintype "passive"))
    )
    (net (code "71") (name "/LADDR3") (class "Default")
      (node (ref "J1") (pin "7") (pinfunction "7_7") (pintype "passive"))
    )
    (net (code "72") (name "/LADDR4") (class "Default")
      (node (ref "J1") (pin "8") (pinfunction "8_8") (pintype "passive"))
    )
    (net (code "73") (name "/LADDR5") (class "Default")
      (node (ref "J1") (pin "5") (pinfunction "5_5") (pintype "passive"))
    )
    (net (code "74") (name "/LADDR6") (class "Default")
      (node (ref "J1") (pin "6") (pinfunction "6_6") (pintype "passive"))
    )
    (net (code "75") (name "/LADDR7") (class "Default")
      (node (ref "J1") (pin "3") (pinfunction "3_3") (pintype "passive"))
    )
    (net (code "76") (name "/LADDR8") (class "Default")
      (node (ref "J1") (pin "4") (pinfunction "4_4") (pintype "passive"))
    )
    (net (code "77") (name "/LADDR9") (class "Default")
      (node (ref "J1") (pin "186") (pinfunction "186_186") (pintype "passive"))
    )
    (net (code "78") (name "/LADDR10") (class "Default")
      (node (ref "J1") (pin "185") (pinfunction "185_185") (pintype "passive"))
    )
    (net (code "79") (name "/LADDR11") (class "Default")
      (node (ref "J1") (pin "184") (pinfunction "184_184") (pintype "passive"))
    )
    (net (code "80") (name "/LADDR12") (class "Default")
      (node (ref "J1") (pin "183") (pinfunction "183_183") (pintype "passive"))
    )
    (net (code "81") (name "/LADDR13") (class "Default")
      (node (ref "J1") (pin "182") (pinfunction "182_182") (pintype "passive"))
    )
    (net (code "82") (name "/LADDR14") (class "Default")
      (node (ref "J1") (pin "181") (pinfunction "181_181") (pintype "passive"))
    )
    (net (code "83") (name "/LADDR15") (class "Default")
      (node (ref "J1") (pin "180") (pinfunction "180_180") (pintype "passive"))
    )
    (net (code "84") (name "/LADDR16") (class "Default")
      (node (ref "J1") (pin "179") (pinfunction "179_179") (pintype "passive"))
    )
    (net (code "85") (name "/LADDR17") (class "Default")
      (node (ref "J1") (pin "178") (pinfunction "178_178") (pintype "passive"))
    )
    (net (code "86") (name "/LADDR18") (class "Default")
      (node (ref "J1") (pin "177") (pinfunction "177_177") (pintype "passive"))
    )
    (net (code "87") (name "/LADDR19") (class "Default")
      (node (ref "J1") (pin "176") (pinfunction "176_176") (pintype "passive"))
    )
    (net (code "88") (name "/LADDR20") (class "Default")
      (node (ref "J1") (pin "175") (pinfunction "175_175") (pintype "passive"))
    )
    (net (code "89") (name "/LAN2_LNK") (class "Default")
      (node (ref "R76") (pin "2") (pinfunction "2_2") (pintype "passive"))
      (node (ref "U1") (pin "38") (pinfunction "LED2_38") (pintype "passive"))
    )
    (net (code "90") (name "/LAN2_SPD") (class "Default")
      (node (ref "R77") (pin "2") (pinfunction "2_2") (pintype "passive"))
      (node (ref "U1") (pin "39") (pinfunction "LED1_39") (pintype "passive"))
    )
    (net (code "91") (name "/LDATA0") (class "Default")
      (node (ref "J1") (pin "187") (pinfunction "187_187") (pintype "passive"))
      (node (ref "U1") (pin "18") (pinfunction "SD0_18") (pintype "passive"))
    )
    (net (code "92") (name "/LDATA1") (class "Default")
      (node (ref "J1") (pin "188") (pinfunction "188_188") (pintype "passive"))
      (node (ref "U1") (pin "17") (pinfunction "SD1_17") (pintype "passive"))
    )
    (net (code "93") (name "/LDATA2") (class "Default")
      (node (ref "J1") (pin "189") (pinfunction "189_189") (pintype "passive"))
      (node (ref "U1") (pin "16") (pinfunction "SD2_16") (pintype "passive"))
    )
    (net (code "94") (name "/LDATA3") (class "Default")
      (node (ref "J1") (pin "190") (pinfunction "190_190") (pintype "passive"))
      (node (ref "U1") (pin "14") (pinfunction "SD3_14") (pintype "passive"))
    )
    (net (code "95") (name "/LDATA4") (class "Default")
      (node (ref "J1") (pin "191") (pinfunction "191_191") (pintype "passive"))
      (node (ref "U1") (pin "13") (pinfunction "SD4_13") (pintype "passive"))
    )
    (net (code "96") (name "/LDATA5") (class "Default")
      (node (ref "J1") (pin "192") (pinfunction "192_192") (pintype "passive"))
      (node (ref "U1") (pin "12") (pinfunction "SD5_12") (pintype "passive"))
    )
    (net (code "97") (name "/LDATA6") (class "Default")
      (node (ref "J1") (pin "1") (pinfunction "1_1") (pintype "passive"))
      (node (ref "U1") (pin "11") (pinfunction "SD6_11") (pintype "passive"))
    )
    (net (code "98") (name "/LDATA7") (class "Default")
      (node (ref "J1") (pin "2") (pinfunction "2_2") (pintype "passive"))
      (node (ref "U1") (pin "10") (pinfunction "SD7_10") (pintype "passive"))
    )
    (net (code "99") (name "/LDATA8") (class "Default")
      (node (ref "J1") (pin "163") (pinfunction "163_163") (pintype "passive"))
      (node (ref "U1") (pin "31") (pinfunction "SD8_31") (pintype "passive"))
    )
    (net (code "100") (name "/LDATA9") (class "Default")
      (node (ref "J1") (pin "164") (pinfunction "164_164") (pintype "passive"))
      (node (ref "U1") (pin "29") (pinfunction "SD9_29") (pintype "passive"))
    )
    (net (code "101") (name "/LDATA10") (class "Default")
      (node (ref "J1") (pin "165") (pinfunction "165_165") (pintype "passive"))
      (node (ref "U1") (pin "28") (pinfunction "SD10_28") (pintype "passive"))
    )
    (net (code "102") (name "/LDATA11") (class "Default")
      (node (ref "J1") (pin "166") (pinfunction "166_166") (pintype "passive"))
      (node (ref "U1") (pin "27") (pinfunction "SD11_27") (pintype "passive"))
    )
    (net (code "103") (name "/LDATA12") (class "Default")
      (node (ref "J1") (pin "167") (pinfunction "167_167") (pintype "passive"))
      (node (ref "U1") (pin "26") (pinfunction "SD12_26") (pintype "passive"))
    )
    (net (code "104") (name "/LDATA13") (class "Default")
      (node (ref "J1") (pin "168") (pinfunction "168_168") (pintype "passive"))
      (node (ref "U1") (pin "25") (pinfunction "SD13_25") (pintype "passive"))
    )
    (net (code "105") (name "/LDATA14") (class "Default")
      (node (ref "J1") (pin "169") (pinfunction "169_169") (pintype "passive"))
      (node (ref "U1") (pin "24") (pinfunction "SD14_24") (pintype "passive"))
    )
    (net (code "106") (name "/LDATA15") (class "Default")
      (node (ref "J1") (pin "170") (pinfunction "170_170") (pintype "passive"))
      (node (ref "U1") (pin "22") (pinfunction "SD15_22") (pintype "passive"))
    )
    (net (code "107") (name "/LnOE") (class "Default")
      (node (ref "J1") (pin "174") (pinfunction "174_174") (pintype "passive"))
      (node (ref "U1") (pin "35") (pinfunction "nIOR_35") (pintype "passive"))
    )
    (net (code "108") (name "/LnWBE1") (class "Default")
      (node (ref "J1") (pin "158") (pinfunction "158_158") (pintype "passive"))
    )
    (net (code "109") (name "/LnWE") (class "Default")
      (node (ref "J1") (pin "173") (pinfunction "173_173") (pintype "passive"))
      (node (ref "U1") (pin "36") (pinfunction "nIOW_36") (pintype "passive"))
    )
    (net (code "110") (name "/MC-AUDIO+") (class "Default")
      (node (ref "C32") (pin "2") (pinfunction "2_2") (pintype "passive"))
      (node (ref "CZ1") (pin "D16") (pinfunction "D16_D16") (pintype "passive"))
    )
    (net (code "111") (name "/MVB485A") (class "Default")
      (node (ref "CZ1") (pin "B24") (pinfunction "B24_B24") (pintype "passive"))
      (node (ref "JP3") (pin "1") (pintype "passive"))
      (node (ref "R85") (pin "2") (pinfunction "2_2") (pintype "passive"))
      (node (ref "U29") (pin "1") (pinfunction "RX+_1") (pintype "passive"))
    )
    (net (code "112") (name "/MVB485B") (class "Default")
      (node (ref "CZ1") (pin "D24") (pinfunction "D24_D24") (pintype "passive"))
      (node (ref "R84") (pin "1") (pinfunction "1_1") (pintype "passive"))
      (node (ref "R86") (pin "2") (pinfunction "2_2") (pintype "passive"))
      (node (ref "U29") (pin "4") (pinfunction "RX-_4") (pintype "passive"))
    )
    (net (code "113") (name "/OCC-ACT") (class "Default")
      (node (ref "CZ1") (pin "B12") (pinfunction "B12_B12") (pintype "passive"))
      (node (ref "D10") (pin "K") (pinfunction "K_K") (pintype "passive"))
    )
    (net (code "114") (name "/OCC-AUDIO+") (class "Default")
      (node (ref "C31") (pin "2") (pinfunction "2_2") (pintype "passive"))
      (node (ref "CZ1") (pin "D14") (pinfunction "D14_D14") (pintype "passive"))
    )
    (net (code "115") (name "/OM3") (class "Default")
      (node (ref "J1") (pin "74") (pinfunction "74_74") (pintype "passive"))
    )
    (net (code "116") (name "/R-OPEN") (class "Default")
      (node (ref "CZ1") (pin "D28") (pinfunction "D28_D28") (pintype "passive"))
      (node (ref "D8") (pin "K") (pinfunction "K_K") (pintype "passive"))
    )
    (net (code "117") (name "/REF") (class "Default")
      (node (ref "C34") (pin "1") (pinfunction "1_1") (pintype "passive"))
      (node (ref "C42") (pin "1") (pinfunction "1_1") (pintype "passive"))
      (node (ref "R21") (pin "2") (pinfunction "2_2") (pintype "passive"))
      (node (ref "R22") (pin "1") (pinfunction "1_1") (pintype "passive"))
      (node (ref "R23") (pin "1") (pinfunction "1_1") (pintype "passive"))
      (node (ref "R24") (pin "1") (pinfunction "1_1") (pintype "passive"))
    )
    (net (code "118") (name "/RS485_EN") (class "Default")
      (node (ref "J1") (pin "11") (pinfunction "11_11") (pintype "passive"))
      (node (ref "R79") (pin "1") (pinfunction "1_1") (pintype "passive"))
    )
    (net (code "119") (name "/RS485_RX") (class "Default")
      (node (ref "J1") (pin "35") (pinfunction "35_35") (pintype "passive"))
      (node (ref "R78") (pin "1") (pinfunction "1_1") (pintype "passive"))
      (node (ref "U25") (pin "6") (pintype "passive"))
    )
    (net (code "120") (name "/RS485_TX") (class "Default")
      (node (ref "J1") (pin "36") (pinfunction "36_36") (pintype "passive"))
      (node (ref "R80") (pin "1") (pinfunction "1_1") (pintype "passive"))
    )
    (net (code "121") (name "/RTSn1") (class "Default")
      (node (ref "J1") (pin "26") (pinfunction "26_26") (pintype "passive"))
    )
    (net (code "122") (name "/RX0_N") (class "Default")
      (node (ref "D27") (pin "K") (pinfunction "2_K") (pintype "passive"))
      (node (ref "R8") (pin "2") (pinfunction "2_2") (pintype "passive"))
      (node (ref "U1") (pin "4") (pinfunction "RX-_4") (pintype "passive"))
      (node (ref "U4") (pin "6") (pinfunction "TDP_6") (pintype "passive"))
    )
    (net (code "123") (name "/RX0_P") (class "Default")
      (node (ref "D28") (pin "K") (pinfunction "2_K") (pintype "passive"))
      (node (ref "R7") (pin "2") (pinfunction "2_2") (pintype "passive"))
      (node (ref "U1") (pin "3") (pinfunction "RX+_3") (pintype "passive"))
      (node (ref "U4") (pin "8") (pinfunction "RDN_8") (pintype "passive"))
    )
    (net (code "124") (name "/RX1_N") (class "Default")
      (node (ref "CZ1") (pin "D20") (pinfunction "D20_D20") (pintype "passive"))
      (node (ref "D12") (pin "A") (pinfunction "1_A") (pintype "passive"))
      (node (ref "J2") (pin "4") (pinfunction "4_4") (pintype "passive"))
      (node (ref "U4") (pin "9") (pinfunction "RXN_9") (pintype "passive"))
    )
    (net (code "125") (name "/RX1_P") (class "Default")
      (node (ref "CZ1") (pin "Z18") (pinfunction "Z18_Z18") (pintype "passive"))
      (node (ref "D12") (pin "K") (pinfunction "2_K") (pintype "passive"))
      (node (ref "J2") (pin "3") (pinfunction "3_3") (pintype "passive"))
      (node (ref "U4") (pin "11") (pinfunction "RXP_11") (pintype "passive"))
    )
    (net (code "126") (name "/RXD0") (class "Default")
      (node (ref "J1") (pin "37") (pinfunction "37_37") (pintype "passive"))
      (node (ref "J4") (pin "3") (pinfunction "3_3") (pintype "passive"))
    )
    (net (code "127") (name "/RXD2") (class "Default")
      (node (ref "J1") (pin "33") (pinfunction "33_33") (pintype "passive"))
    )
    (net (code "128") (name "/RXD3") (class "Default")
      (node (ref "J1") (pin "23") (pinfunction "23_23") (pintype "passive"))
    )
    (net (code "129") (name "/RnB") (class "Default")
      (node (ref "J1") (pin "17") (pinfunction "17_17") (pintype "passive"))
    )
    (net (code "130") (name "/SDCLK") (class "Default")
      (node (ref "J1") (pin "83") (pinfunction "83_83") (pintype "passive"))
      (node (ref "J3") (pin "5") (pinfunction "CLK_5") (pintype "passive"))
      (node (ref "R57") (pin "2") (pinfunction "BOT_2") (pintype "passive"))
    )
    (net (code "131") (name "/SDCMD") (class "Default")
      (node (ref "J1") (pin "82") (pinfunction "82_82") (pintype "passive"))
      (node (ref "J3") (pin "2") (pinfunction "CMD_2") (pintype "passive"))
      (node (ref "R58") (pin "2") (pinfunction "BOT_2") (pintype "passive"))
    )
    (net (code "132") (name "/SDDATA0") (class "Default")
      (node (ref "J1") (pin "84") (pinfunction "84_84") (pintype "passive"))
      (node (ref "J3") (pin "7") (pinfunction "DAT0_7") (pintype "passive"))
      (node (ref "R56") (pin "2") (pinfunction "BOT_2") (pintype "passive"))
    )
    (net (code "133") (name "/SDDATA1") (class "Default")
      (node (ref "J1") (pin "85") (pinfunction "85_85") (pintype "passive"))
      (node (ref "J3") (pin "8") (pinfunction "DAT1_8") (pintype "passive"))
      (node (ref "R55") (pin "2") (pinfunction "BOT_2") (pintype "passive"))
    )
    (net (code "134") (name "/SDDATA2") (class "Default")
      (node (ref "J1") (pin "80") (pinfunction "80_80") (pintype "passive"))
      (node (ref "J3") (pin "9") (pinfunction "DAT2_9") (pintype "passive"))
      (node (ref "R60") (pin "2") (pinfunction "BOT_2") (pintype "passive"))
    )
    (net (code "135") (name "/SDDATA3") (class "Default")
      (node (ref "J1") (pin "81") (pinfunction "81_81") (pintype "passive"))
      (node (ref "J3") (pin "1") (pinfunction "CD/DAT3_1") (pintype "passive"))
      (node (ref "R59") (pin "2") (pinfunction "BOT_2") (pintype "passive"))
    )
    (net (code "136") (name "/SPEED") (class "Default")
      (node (ref "CZ1") (pin "B28") (pinfunction "B28_B28") (pintype "passive"))
      (node (ref "D6") (pin "K") (pinfunction "K_K") (pintype "passive"))
    )
    (net (code "137") (name "/SPICLK") (class "Default")
      (node (ref "J1") (pin "69") (pinfunction "69_69") (pintype "passive"))
    )
    (net (code "138") (name "/SPIMISO") (class "Default")
      (node (ref "J1") (pin "67") (pinfunction "67_67") (pintype "passive"))
    )
    (net (code "139") (name "/SPIMOSI") (class "Default")
      (node (ref "J1") (pin "70") (pinfunction "70_70") (pintype "passive"))
    )
    (net (code "140") (name "/TCK") (class "Default")
      (node (ref "J1") (pin "31") (pinfunction "31_31") (pintype "passive"))
      (node (ref "J5") (pin "9") (pinfunction "9_9") (pintype "passive"))
      (node (ref "R49") (pin "2") (pinfunction "BOT_2") (pintype "passive"))
    )
    (net (code "141") (name "/TDI") (class "Default")
      (node (ref "J1") (pin "30") (pinfunction "30_30") (pintype "passive"))
      (node (ref "J5") (pin "5") (pinfunction "5_5") (pintype "passive"))
      (node (ref "R51") (pin "2") (pinfunction "BOT_2") (pintype "passive"))
    )
    (net (code "142") (name "/TDO") (class "Default")
      (node (ref "J1") (pin "29") (pinfunction "29_29") (pintype "passive"))
      (node (ref "J5") (pin "13") (pinfunction "13_13") (pintype "passive"))
    )
    (net (code "143") (name "/TMS") (class "Default")
      (node (ref "J1") (pin "32") (pinfunction "32_32") (pintype "passive"))
      (node (ref "J5") (pin "7") (pinfunction "7_7") (pintype "passive"))
      (node (ref "R50") (pin "2") (pinfunction "BOT_2") (pintype "passive"))
    )
    (net (code "144") (name "/TOUT0") (class "Default")
      (node (ref "J1") (pin "137") (pinfunction "137_137") (pintype "passive"))
    )
    (net (code "145") (name "/TOUT1") (class "Default")
      (node (ref "J1") (pin "136") (pinfunction "136_136") (pintype "passive"))
    )
    (net (code "146") (name "/TSXM") (class "Default")
      (node (ref "J1") (pin "97") (pinfunction "97_97") (pintype "passive"))
    )
    (net (code "147") (name "/TSXP") (class "Default")
      (node (ref "J1") (pin "96") (pinfunction "96_96") (pintype "passive"))
    )
    (net (code "148") (name "/TSYM") (class "Default")
      (node (ref "J1") (pin "99") (pinfunction "99_99") (pintype "passive"))
    )
    (net (code "149") (name "/TSYP") (class "Default")
      (node (ref "J1") (pin "98") (pinfunction "98_98") (pintype "passive"))
    )
    (net (code "150") (name "/TX0_N") (class "Default")
      (node (ref "D26") (pin "K") (pinfunction "2_K") (pintype "passive"))
      (node (ref "R6") (pin "1") (pinfunction "1_1") (pintype "passive"))
      (node (ref "U1") (pin "8") (pinfunction "TX-_8") (pintype "passive"))
      (node (ref "U4") (pin "1") (pinfunction "TDP_1") (pintype "passive"))
    )
    (net (code "151") (name "/TX0_P") (class "Default")
      (node (ref "D25") (pin "K") (pinfunction "2_K") (pintype "passive"))
      (node (ref "R5") (pin "1") (pinfunction "1_1") (pintype "passive"))
      (node (ref "U1") (pin "7") (pinfunction "TX+_7") (pintype "passive"))
      (node (ref "U4") (pin "3") (pinfunction "TDN_3") (pintype "passive"))
    )
    (net (code "152") (name "/TX1_N") (class "Default")
      (node (ref "CZ1") (pin "B18") (pinfunction "B18_B18") (pintype "passive"))
      (node (ref "D11") (pin "A") (pinfunction "1_A") (pintype "passive"))
      (node (ref "J2") (pin "2") (pinfunction "2_2") (pintype "passive"))
      (node (ref "U4") (pin "14") (pinfunction "TXN_14") (pintype "passive"))
    )
    (net (code "153") (name "/TX1_P") (class "Default")
      (node (ref "CZ1") (pin "D18") (pinfunction "D18_D18") (pintype "passive"))
      (node (ref "D11") (pin "K") (pinfunction "2_K") (pintype "passive"))
      (node (ref "J2") (pin "1") (pinfunction "1_1") (pintype "passive"))
      (node (ref "U4") (pin "16") (pinfunction "TXP_16") (pintype "passive"))
    )
    (net (code "154") (name "/TXD0") (class "Default")
      (node (ref "J1") (pin "38") (pinfunction "38_38") (pintype "passive"))
      (node (ref "J4") (pin "2") (pinfunction "2_2") (pintype "passive"))
    )
    (net (code "155") (name "/TXD2") (class "Default")
      (node (ref "J1") (pin "34") (pinfunction "34_34") (pintype "passive"))
    )
    (net (code "156") (name "/TXD3") (class "Default")
      (node (ref "J1") (pin "24") (pinfunction "24_24") (pintype "passive"))
    )
    (net (code "157") (name "/USB_EN") (class "Default")
      (node (ref "J1") (pin "57") (pinfunction "57_57") (pintype "passive"))
    )
    (net (code "158") (name "/VCLK") (class "Default")
      (node (ref "J1") (pin "100") (pinfunction "100_100") (pintype "passive"))
    )
    (net (code "159") (name "/VD0") (class "Default")
      (node (ref "J1") (pin "129") (pinfunction "129_129") (pintype "passive"))
    )
    (net (code "160") (name "/VD1") (class "Default")
      (node (ref "J1") (pin "128") (pinfunction "128_128") (pintype "passive"))
    )
    (net (code "161") (name "/VD2") (class "Default")
      (node (ref "J1") (pin "127") (pinfunction "127_127") (pintype "passive"))
    )
    (net (code "162") (name "/VD3") (class "Default")
      (node (ref "J1") (pin "126") (pinfunction "126_126") (pintype "passive"))
    )
    (net (code "163") (name "/VD4") (class "Default")
      (node (ref "J1") (pin "125") (pinfunction "125_125") (pintype "passive"))
    )
    (net (code "164") (name "/VD5") (class "Default")
      (node (ref "J1") (pin "124") (pinfunction "124_124") (pintype "passive"))
    )
    (net (code "165") (name "/VD6") (class "Default")
      (node (ref "J1") (pin "123") (pinfunction "123_123") (pintype "passive"))
    )
    (net (code "166") (name "/VD7") (class "Default")
      (node (ref "J1") (pin "122") (pinfunction "122_122") (pintype "passive"))
    )
    (net (code "167") (name "/VD8") (class "Default")
      (node (ref "J1") (pin "121") (pinfunction "121_121") (pintype "passive"))
    )
    (net (code "168") (name "/VD9") (class "Default")
      (node (ref "J1") (pin "120") (pinfunction "120_120") (pintype "passive"))
    )
    (net (code "169") (name "/VD10") (class "Default")
      (node (ref "J1") (pin "119") (pinfunction "119_119") (pintype "passive"))
    )
    (net (code "170") (name "/VD11") (class "Default")
      (node (ref "J1") (pin "118") (pinfunction "118_118") (pintype "passive"))
    )
    (net (code "171") (name "/VD12") (class "Default")
      (node (ref "J1") (pin "117") (pinfunction "117_117") (pintype "passive"))
    )
    (net (code "172") (name "/VD13") (class "Default")
      (node (ref "J1") (pin "116") (pinfunction "116_116") (pintype "passive"))
    )
    (net (code "173") (name "/VD14") (class "Default")
      (node (ref "J1") (pin "115") (pinfunction "115_115") (pintype "passive"))
    )
    (net (code "174") (name "/VD15") (class "Default")
      (node (ref "J1") (pin "114") (pinfunction "114_114") (pintype "passive"))
    )
    (net (code "175") (name "/VD16") (class "Default")
      (node (ref "J1") (pin "113") (pinfunction "113_113") (pintype "passive"))
    )
    (net (code "176") (name "/VD17") (class "Default")
      (node (ref "J1") (pin "112") (pinfunction "112_112") (pintype "passive"))
    )
    (net (code "177") (name "/VD18") (class "Default")
      (node (ref "J1") (pin "111") (pinfunction "111_111") (pintype "passive"))
    )
    (net (code "178") (name "/VD19") (class "Default")
      (node (ref "J1") (pin "110") (pinfunction "110_110") (pintype "passive"))
    )
    (net (code "179") (name "/VD20") (class "Default")
      (node (ref "J1") (pin "109") (pinfunction "109_109") (pintype "passive"))
    )
    (net (code "180") (name "/VD21") (class "Default")
      (node (ref "J1") (pin "108") (pinfunction "108_108") (pintype "passive"))
    )
    (net (code "181") (name "/VD22") (class "Default")
      (node (ref "J1") (pin "107") (pinfunction "107_107") (pintype "passive"))
    )
    (net (code "182") (name "/VD23") (class "Default")
      (node (ref "J1") (pin "106") (pinfunction "106_106") (pintype "passive"))
    )
    (net (code "183") (name "/VDDRTC") (class "Default")
      (node (ref "J1") (pin "58") (pinfunction "58_58") (pintype "passive"))
      (node (ref "R1") (pin "2") (pintype "passive"))
    )
    (net (code "184") (name "/VFRAME") (class "Default")
      (node (ref "J1") (pin "102") (pinfunction "102_102") (pintype "passive"))
    )
    (net (code "185") (name "/VLINE") (class "Default")
      (node (ref "J1") (pin "101") (pinfunction "101_101") (pintype "passive"))
    )
    (net (code "186") (name "/VM") (class "Default")
      (node (ref "J1") (pin "103") (pinfunction "103_103") (pintype "passive"))
    )
    (net (code "187") (name "/VREF") (class "Default")
      (node (ref "J1") (pin "73") (pinfunction "73_73") (pintype "passive"))
    )
    (net (code "188") (name "/WP_SD") (class "Default")
      (node (ref "J1") (pin "86") (pinfunction "86_86") (pintype "passive"))
      (node (ref "J3") (pin "10") (pinfunction "WP_10") (pintype "passive"))
      (node (ref "R62") (pin "2") (pinfunction "BOT_2") (pintype "passive"))
    )
    (net (code "189") (name "/nBATF") (class "Default")
      (node (ref "J1") (pin "21") (pinfunction "21_21") (pintype "passive"))
    )
    (net (code "190") (name "/nCD_SD") (class "Default")
      (node (ref "J1") (pin "79") (pinfunction "79_79") (pintype "passive"))
      (node (ref "J3") (pin "11") (pinfunction "nCD_11") (pintype "passive"))
      (node (ref "R61") (pin "2") (pinfunction "BOT_2") (pintype "passive"))
    )
    (net (code "191") (name "/nCTS0") (class "Default")
      (node (ref "J1") (pin "40") (pinfunction "40_40") (pintype "passive"))
    )
    (net (code "192") (name "/nGCS3") (class "Default")
      (node (ref "J1") (pin "154") (pinfunction "154_154") (pintype "passive"))
    )
    (net (code "193") (name "/nGCS5") (class "Default")
      (node (ref "J1") (pin "156") (pinfunction "156_156") (pintype "passive"))
    )
    (net (code "194") (name "/nGCS7") (class "Default")
      (node (ref "J1") (pin "157") (pinfunction "157_157") (pintype "passive"))
    )
    (net (code "195") (name "/nIDE_CS1") (class "Default")
      (node (ref "J1") (pin "152") (pinfunction "152_152") (pintype "passive"))
    )
    (net (code "196") (name "/nIDE_CS2") (class "Default")
      (node (ref "J1") (pin "153") (pinfunction "153_153") (pintype "passive"))
    )
    (net (code "197") (name "/nLAN_CS2") (class "Default")
      (node (ref "J1") (pin "155") (pinfunction "155_155") (pintype "passive"))
      (node (ref "U1") (pin "37") (pinfunction "nCS_37") (pintype "passive"))
    )
    (net (code "198") (name "/nLED_1") (class "Default")
      (node (ref "J1") (pin "132") (pinfunction "132_132") (pintype "passive"))
    )
    (net (code "199") (name "/nLED_2") (class "Default")
      (node (ref "J1") (pin "133") (pinfunction "133_133") (pintype "passive"))
    )
    (net (code "200") (name "/nLED_3") (class "Default")
      (node (ref "J1") (pin "134") (pinfunction "134_134") (pintype "passive"))
    )
    (net (code "201") (name "/nLED_4") (class "Default")
      (node (ref "J1") (pin "135") (pinfunction "135_135") (pintype "passive"))
    )
    (net (code "202") (name "/nRESET") (class "Default")
      (node (ref "J1") (pin "28") (pinfunction "28_28") (pintype "passive"))
      (node (ref "J5") (pin "15") (pinfunction "15_15") (pintype "passive"))
      (node (ref "R53") (pin "2") (pinfunction "BOT_2") (pintype "passive"))
      (node (ref "U1") (pin "40") (pinfunction "PWRST_40") (pintype "passive"))
      (node (ref "U21") (pin "7") (pinfunction "RESET_7") (pintype "passive"))
    )
    (net (code "203") (name "/nRSTOUT") (class "Default")
      (node (ref "J1") (pin "22") (pinfunction "22_22") (pintype "passive"))
    )
    (net (code "204") (name "/nRTS0") (class "Default")
      (node (ref "J1") (pin "39") (pinfunction "39_39") (pintype "passive"))
    )
    (net (code "205") (name "/nSS_SPI") (class "Default")
      (node (ref "J1") (pin "68") (pinfunction "68_68") (pintype "passive"))
    )
    (net (code "206") (name "/nTRST") (class "Default")
      (node (ref "J1") (pin "27") (pinfunction "27_27") (pintype "passive"))
      (node (ref "J5") (pin "3") (pinfunction "3_3") (pintype "passive"))
      (node (ref "R52") (pin "2") (pinfunction "BOT_2") (pintype "passive"))
      (node (ref "R53") (pin "1") (pinfunction "TOP_1") (pintype "passive"))
    )
    (net (code "207") (name "/nWAIT") (class "Default")
      (node (ref "J1") (pin "151") (pinfunction "151_151") (pintype "passive"))
    )
    (net (code "208") (name "24V") (class "Default")
      (node (ref "C33") (pin "1") (pinfunction "1_1") (pintype "passive"))
      (node (ref "C41") (pin "1") (pinfunction "1_1") (pintype "passive"))
      (node (ref "C48") (pin "1") (pinfunction "1_1") (pintype "passive"))
      (node (ref "C49") (pin "1") (pinfunction "1_1") (pintype "passive"))
      (node (ref "D14") (pin "K") (pinfunction "K_K") (pintype "passive"))
      (node (ref "D15") (pin "K") (pintype "passive"))
      (node (ref "L6") (pin "1") (pinfunction "1_1") (pintype "passive"))
      (node (ref "R25") (pin "2") (pinfunction "2_2") (pintype "passive"))
      (node (ref "R26") (pin "2") (pinfunction "2_2") (pintype "passive"))
      (node (ref "R27") (pin "2") (pinfunction "2_2") (pintype "passive"))
      (node (ref "R28") (pin "2") (pinfunction "2_2") (pintype "passive"))
      (node (ref "R29") (pin "2") (pinfunction "2_2") (pintype "passive"))
      (node (ref "R30") (pin "2") (pinfunction "2_2") (pintype "passive"))
      (node (ref "R31") (pin "2") (pinfunction "2_2") (pintype "passive"))
      (node (ref "R32") (pin "2") (pinfunction "2_2") (pintype "passive"))
      (node (ref "R33") (pin "2") (pinfunction "2_2") (pintype "passive"))
      (node (ref "R34") (pin "2") (pinfunction "2_2") (pintype "passive"))
      (node (ref "U23") (pin "1") (pinfunction "VIN_1") (pintype "passive"))
    )
    (net (code "209") (name "24V_IN") (class "Default")
      (node (ref "BX1") (pin "2") (pinfunction "2_2") (pintype "passive"))
      (node (ref "CZ1") (pin "B6") (pinfunction "B6_B6") (pintype "passive"))
      (node (ref "CZ1") (pin "B8") (pinfunction "B8_B8") (pintype "passive"))
      (node (ref "CZ1") (pin "D6") (pinfunction "D6_D6") (pintype "passive"))
      (node (ref "CZ1") (pin "D8") (pinfunction "D8_D8") (pintype "passive"))
      (node (ref "CZ1") (pin "Z6") (pinfunction "Z6_Z6") (pintype "passive"))
      (node (ref "CZ1") (pin "Z8") (pinfunction "Z8_Z8") (pintype "passive"))
    )
    (net (code "210") (name "485-GND") (class "Default")
      (node (ref "C57") (pin "2") (pinfunction "2_2") (pintype "passive"))
      (node (ref "C58") (pin "1") (pinfunction "1_1") (pintype "passive"))
      (node (ref "CZ1") (pin "Z24") (pinfunction "Z24_Z24") (pintype "passive"))
      (node (ref "U26") (pin "5") (pintype "passive"))
      (node (ref "U27") (pin "5") (pintype "passive"))
      (node (ref "U28") (pin "5") (pinfunction "GND_5") (pintype "passive"))
      (node (ref "U30") (pin "3") (pinfunction "485_GND_3") (pintype "passive"))
    )
    (net (code "211") (name "485_+5V") (class "Default")
      (node (ref "C57") (pin "1") (pinfunction "1_1") (pintype "passive"))
      (node (ref "C58") (pin "2") (pinfunction "2_2") (pintype "passive"))
      (node (ref "R82") (pin "1") (pinfunction "1_1") (pintype "passive"))
      (node (ref "R83") (pin "2") (pinfunction "2_2") (pintype "passive"))
      (node (ref "U25") (pin "1") (pintype "passive"))
      (node (ref "U25") (pin "2") (pintype "passive"))
      (node (ref "U26") (pin "7") (pintype "passive"))
      (node (ref "U26") (pin "8") (pintype "passive"))
      (node (ref "U27") (pin "7") (pintype "passive"))
      (node (ref "U27") (pin "8") (pintype "passive"))
      (node (ref "U28") (pin "8") (pinfunction "VCC_8") (pintype "passive"))
      (node (ref "U30") (pin "4") (pinfunction "485_+5V_4") (pintype "passive"))
    )
    (net (code "212") (name "A3.3V") (class "Default")
      (node (ref "C24") (pin "2") (pinfunction "2_2") (pintype "passive"))
      (node (ref "C26") (pin "1") (pinfunction "1_1") (pintype "passive"))
      (node (ref "L4") (pin "2") (pinfunction "2_2") (pintype "passive"))
      (node (ref "U7") (pin "25") (pinfunction "AVDD(DAC)_25") (pintype "passive"))
      (node (ref "U7") (pin "3") (pinfunction "AVDD(ADC)_3") (pintype "passive"))
      (node (ref "U7") (pin "7") (pinfunction "Vpref(ADC)_7") (pintype "passive"))
    )
    (net (code "213") (name "A24V") (class "Default")
      (node (ref "L6") (pin "2") (pinfunction "2_2") (pintype "passive"))
      (node (ref "R23") (pin "2") (pinfunction "2_2") (pintype "passive"))
      (node (ref "U8") (pin "8") (pinfunction "V+_8") (pintype "power_in"))
    )
    (net (code "214") (name "AGND") (class "Default")
      (node (ref "C24") (pin "1") (pinfunction "1_1") (pintype "passive"))
      (node (ref "C26") (pin "2") (pinfunction "2_2") (pintype "passive"))
      (node (ref "C27") (pin "2") (pinfunction "2_2") (pintype "passive"))
      (node (ref "C28") (pin "2") (pinfunction "2_2") (pintype "passive"))
      (node (ref "C34") (pin "2") (pinfunction "2_2") (pintype "passive"))
      (node (ref "C42") (pin "2") (pinfunction "2_2") (pintype "passive"))
      (node (ref "CZ1") (pin "B14") (pinfunction "B14_B14") (pintype "passive"))
      (node (ref "CZ1") (pin "B16") (pinfunction "B16_B16") (pintype "passive"))
      (node (ref "L5") (pin "2") (pinfunction "2_2") (pintype "passive"))
      (node (ref "L7") (pin "2") (pinfunction "2_2") (pintype "passive"))
      (node (ref "R24") (pin "2") (pinfunction "2_2") (pintype "passive"))
      (node (ref "U7") (pin "1") (pinfunction "AVSS(ADC)_1") (pintype "passive"))
      (node (ref "U7") (pin "27") (pinfunction "AVSS(DAC)_27") (pintype "passive"))
      (node (ref "U7") (pin "5") (pinfunction "Vnref(ADC)_5") (pintype "passive"))
      (node (ref "U8") (pin "4") (pinfunction "V-_4") (pintype "power_in"))
    )
    (net (code "215") (name "DGND") (class "Default")
      (node (ref "BAT1") (pin "2") (pinfunction "2_2") (pintype "passive"))
      (node (ref "C1") (pin "2") (pinfunction "2_2") (pintype "passive"))
      (node (ref "C12") (pin "2") (pinfunction "2_2") (pintype "passive"))
      (node (ref "C13") (pin "2") (pinfunction "2_2") (pintype "passive"))
      (node (ref "C2") (pin "2") (pinfunction "2_2") (pintype "passive"))
      (node (ref "C23") (pin "1") (pinfunction "1_1") (pintype "passive"))
      (node (ref "C25") (pin "2") (pinfunction "2_2") (pintype "passive"))
      (node (ref "C3") (pin "1") (pinfunction "1_1") (pintype "passive"))
      (node (ref "C33") (pin "2") (pinfunction "2_2") (pintype "passive"))
      (node (ref "C4") (pin "1") (pinfunction "1_1") (pintype "passive"))
      (node (ref "C41") (pin "2") (pinfunction "2_2") (pintype "passive"))
      (node (ref "C43") (pin "2") (pinfunction "2_2") (pintype "passive"))
      (node (ref "C44") (pin "1") (pinfunction "1_1") (pintype "passive"))
      (node (ref "C45") (pin "2") (pinfunction "2_2") (pintype "passive"))
      (node (ref "C46") (pin "2") (pinfunction "2_2") (pintype "passive"))
      (node (ref "C47") (pin "1") (pinfunction "1_1") (pintype "passive"))
      (node (ref "C48") (pin "2") (pinfunction "2_2") (pintype "passive"))
      (node (ref "C49") (pin "2") (pinfunction "2_2") (pintype "passive"))
      (node (ref "C50") (pin "2") (pinfunction "2_2") (pintype "passive"))
      (node (ref "C51") (pin "2") (pinfunction "2_2") (pintype "passive"))
      (node (ref "C54") (pin "2") (pinfunction "2_2") (pintype "passive"))
      (node (ref "C55") (pin "2") (pinfunction "2_2") (pintype "passive"))
      (node (ref "C56") (pin "2") (pinfunction "2_2") (pintype "passive"))
      (node (ref "CZ1") (pin "B2") (pinfunction "B2_B2") (pintype "passive"))
      (node (ref "CZ1") (pin "B4") (pinfunction "B4_B4") (pintype "passive"))
      (node (ref "CZ1") (pin "D2") (pinfunction "D2_D2") (pintype "passive"))
      (node (ref "CZ1") (pin "D4") (pinfunction "D4_D4") (pintype "passive"))
      (node (ref "CZ1") (pin "Z2") (pinfunction "Z2_Z2") (pintype "passive"))
      (node (ref "CZ1") (pin "Z4") (pinfunction "Z4_Z4") (pintype "passive"))
      (node (ref "D15") (pin "A") (pintype "passive"))
      (node (ref "D16") (pin "A") (pinfunction "A_A") (pintype "passive"))
      (node (ref "D25") (pin "A") (pinfunction "1_A") (pintype "passive"))
      (node (ref "D26") (pin "A") (pinfunction "1_A") (pintype "passive"))
      (node (ref "D27") (pin "A") (pinfunction "1_A") (pintype "passive"))
      (node (ref "D28") (pin "A") (pinfunction "1_A") (pintype "passive"))
      (node (ref "J1") (pin "159") (pinfunction "159_159") (pintype "passive"))
      (node (ref "J1") (pin "160") (pinfunction "160_160") (pintype "passive"))
      (node (ref "J1") (pin "75") (pinfunction "75_75") (pintype "passive"))
      (node (ref "J1") (pin "76") (pinfunction "76_76") (pintype "passive"))
      (node (ref "J1") (pin "77") (pinfunction "77_77") (pintype "passive"))
      (node (ref "J1") (pin "78") (pinfunction "78_78") (pintype "passive"))
      (node (ref "J3") (pin "12") (pinfunction "PAD1_12") (pintype "passive"))
      (node (ref "J3") (pin "13") (pinfunction "PAD2_13") (pintype "passive"))
      (node (ref "J3") (pin "14") (pinfunction "PAD3_14") (pintype "passive"))
      (node (ref "J3") (pin "15") (pinfunction "PAD4_15") (pintype "passive"))
      (node (ref "J3") (pin "3") (pinfunction "VSS1_3") (pintype "passive"))
      (node (ref "J3") (pin "6") (pinfunction "VSS2_6") (pintype "passive"))
      (node (ref "J4") (pin "4") (pinfunction "4_4") (pintype "passive"))
      (node (ref "J5") (pin "10") (pinfunction "10_10") (pintype "passive"))
      (node (ref "J5") (pin "12") (pinfunction "12_12") (pintype "passive"))
      (node (ref "J5") (pin "14") (pinfunction "14_14") (pintype "passive"))
      (node (ref "J5") (pin "16") (pinfunction "16_16") (pintype "passive"))
      (node (ref "J5") (pin "18") (pinfunction "18_18") (pintype "passive"))
      (node (ref "J5") (pin "20") (pinfunction "20_20") (pintype "passive"))
      (node (ref "J5") (pin "4") (pinfunction "4_4") (pintype "passive"))
      (node (ref "J5") (pin "6") (pinfunction "6_6") (pintype "passive"))
      (node (ref "J5") (pin "8") (pinfunction "8_8") (pintype "passive"))
      (node (ref "JP1") (pin "1") (pintype "passive"))
      (node (ref "JP1") (pin "2") (pintype "passive"))
      (node (ref "L2") (pin "1") (pinfunction "1_1") (pintype "passive"))
      (node (ref "L5") (pin "1") (pinfunction "1_1") (pintype "passive"))
      (node (ref "L7") (pin "1") (pinfunction "1_1") (pintype "passive"))
      (node (ref "R13") (pin "1") (pinfunction "1_1") (pintype "passive"))
      (node (ref "R14") (pin "1") (pinfunction "1_1") (pintype "passive"))
      (node (ref "R15") (pin "1") (pinfunction "1_1") (pintype "passive"))
      (node (ref "R16") (pin "1") (pinfunction "1_1") (pintype "passive"))
      (node (ref "R2") (pin "1") (pinfunction "1_1") (pintype "passive"))
      (node (ref "R54") (pin "2") (pinfunction "BOT_2") (pintype "passive"))
      (node (ref "R75") (pin "2") (pinfunction "2_2") (pintype "passive"))
      (node (ref "S1") (pin "1") (pinfunction "1_1") (pintype "passive"))
      (node (ref "U1") (pin "15") (pinfunction "GND0_15") (pintype "passive"))
      (node (ref "U1") (pin "33") (pinfunction "GND1_33") (pintype "passive"))
      (node (ref "U1") (pin "41") (pinfunction "TEST_41") (pintype "passive"))
      (node (ref "U1") (pin "45") (pinfunction "GND2_45") (pintype "passive"))
      (node (ref "U10") (pin "3") (pinfunction "E_3") (pintype "passive"))
      (node (ref "U11") (pin "3") (pinfunction "E_3") (pintype "passive"))
      (node (ref "U12") (pin "3") (pinfunction "E_3") (pintype "passive"))
      (node (ref "U13") (pin "3") (pinfunction "E_3") (pintype "passive"))
      (node (ref "U14") (pin "3") (pinfunction "E_3") (pintype "passive"))
      (node (ref "U15") (pin "3") (pinfunction "E_3") (pintype "passive"))
      (node (ref "U16") (pin "3") (pinfunction "E_3") (pintype "passive"))
      (node (ref "U17") (pin "3") (pinfunction "E_3") (pintype "passive"))
      (node (ref "U18") (pin "3") (pinfunction "E_3") (pintype "passive"))
      (node (ref "U21") (pin "3") (pinfunction "GND_3") (pintype "passive"))
      (node (ref "U22") (pin "1") (pinfunction "A0_1") (pintype "passive"))
      (node (ref "U22") (pin "2") (pinfunction "A1_2") (pintype "passive"))
      (node (ref "U22") (pin "3") (pinfunction "A2_3") (pintype "passive"))
      (node (ref "U22") (pin "8") (pinfunction "VSS_8") (pintype "passive"))
      (node (ref "U23") (pin "3") (pinfunction "GND_3") (pintype "passive"))
      (node (ref "U23") (pin "5") (pinfunction "NC_5") (pintype "passive"))
      (node (ref "U23") (pin "6") (pinfunction "GND_6") (pintype "passive"))
      (node (ref "U24") (pin "1") (pinfunction "GND_1") (pintype "passive"))
      (node (ref "U25") (pin "5") (pintype "passive"))
      (node (ref "U30") (pin "1") (pinfunction "GND_1") (pintype "passive"))
      (node (ref "U7") (pin "11") (pinfunction "DVSS_11") (pintype "passive"))
      (node (ref "U9") (pin "3") (pinfunction "E_3") (pintype "passive"))
    )
    (net (code "216") (name "EGND") (class "Default")
      (node (ref "C21") (pin "2") (pinfunction "2_2") (pintype "passive"))
      (node (ref "CZ1") (pin "B32") (pinfunction "B32_B32") (pintype "passive"))
      (node (ref "CZ1") (pin "D32") (pinfunction "D32_D32") (pintype "passive"))
      (node (ref "CZ1") (pin "Z32") (pinfunction "Z32_Z32") (pintype "passive"))
      (node (ref "U29") (pin "6") (pinfunction "GND_6") (pintype "passive"))
    )
    (net (code "217") (name "NET_AGND") (class "Default")
      (node (ref "C14") (pin "2") (pinfunction "2_2") (pintype "passive"))
      (node (ref "C16") (pin "2") (pinfunction "2_2") (pintype "passive"))
      (node (ref "C18") (pin "2") (pinfunction "2_2") (pintype "passive"))
      (node (ref "C19") (pin "1") (pinfunction "1_1") (pintype "passive"))
      (node (ref "C5") (pin "2") (pinfunction "2_2") (pintype "passive"))
      (node (ref "C6") (pin "2") (pinfunction "2_2") (pintype "passive"))
      (node (ref "L2") (pin "2") (pinfunction "2_2") (pintype "passive"))
      (node (ref "R3") (pin "2") (pinfunction "2_2") (pintype "passive"))
      (node (ref "U1") (pin "47") (pinfunction "RXGND1_47") (pintype "passive"))
      (node (ref "U1") (pin "48") (pinfunction "BGGND_48") (pintype "passive"))
      (node (ref "U1") (pin "5") (pinfunction "RXGND0_5") (pintype "passive"))
      (node (ref "U1") (pin "6") (pinfunction "TXGND_6") (pintype "passive"))
    )
    (net (code "218") (name "NET_AVDD25V") (class "Default")
      (node (ref "C5") (pin "1") (pinfunction "1_1") (pintype "passive"))
      (node (ref "C6") (pin "1") (pinfunction "1_1") (pintype "passive"))
      (node (ref "U1") (pin "2") (pinfunction "RXVDD25_2") (pintype "passive"))
      (node (ref "U1") (pin "9") (pinfunction "TXVDD25_9") (pintype "passive"))
      (node (ref "U4") (pin "2") (pinfunction "TDC_2") (pintype "passive"))
      (node (ref "U4") (pin "7") (pinfunction "RDC_7") (pintype "passive"))
    )
    (net (code "219") (name "NET_AVDD33V") (class "Default")
      (node (ref "C14") (pin "1") (pinfunction "1_1") (pintype "passive"))
      (node (ref "C16") (pin "1") (pinfunction "1_1") (pintype "passive"))
      (node (ref "L1") (pin "2") (pinfunction "2_2") (pintype "passive"))
      (node (ref "R4") (pin "2") (pinfunction "2_2") (pintype "passive"))
      (node (ref "U1") (pin "23") (pinfunction "VDD0_23") (pintype "passive"))
      (node (ref "U1") (pin "30") (pinfunction "VDD1_30") (pintype "passive"))
      (node (ref "U1") (pin "42") (pinfunction "VDD2_42") (pintype "passive"))
    )
    (net (code "220") (name "Net-(BAT1-Pad1)") (class "Default")
      (node (ref "BAT1") (pin "1") (pinfunction "1_1") (pintype "passive"))
      (node (ref "D30") (pin "A") (pinfunction "A_A") (pintype "passive"))
    )
    (net (code "221") (name "Net-(BX1-Pad1)") (class "Default")
      (node (ref "BX1") (pin "1") (pinfunction "1_1") (pintype "passive"))
      (node (ref "D14") (pin "A") (pinfunction "A_A") (pintype "passive"))
    )
    (net (code "222") (name "Net-(C18-Pad1)") (class "Default")
      (node (ref "C18") (pin "1") (pinfunction "1_1") (pintype "passive"))
      (node (ref "R5") (pin "2") (pinfunction "2_2") (pintype "passive"))
      (node (ref "R6") (pin "2") (pinfunction "2_2") (pintype "passive"))
    )
    (net (code "223") (name "Net-(C19-Pad2)") (class "Default")
      (node (ref "C19") (pin "2") (pinfunction "2_2") (pintype "passive"))
      (node (ref "R7") (pin "1") (pinfunction "1_1") (pintype "passive"))
      (node (ref "R8") (pin "1") (pinfunction "1_1") (pintype "passive"))
    )
    (net (code "224") (name "Net-(C21-Pad1)") (class "Default")
      (node (ref "C21") (pin "1") (pinfunction "1_1") (pintype "passive"))
      (node (ref "R10") (pin "1") (pinfunction "1_1") (pintype "passive"))
      (node (ref "R9") (pin "1") (pinfunction "1_1") (pintype "passive"))
    )
    (net (code "225") (name "Net-(C29-Pad2)") (class "Default")
      (node (ref "C29") (pin "2") (pinfunction "2_2") (pintype "passive"))
      (node (ref "R11") (pin "1") (pinfunction "1_1") (pintype "passive"))
    )
    (net (code "226") (name "Net-(C30-Pad2)") (class "Default")
      (node (ref "C30") (pin "2") (pinfunction "2_2") (pintype "passive"))
      (node (ref "R12") (pin "1") (pinfunction "1_1") (pintype "passive"))
    )
    (net (code "227") (name "Net-(C31-Pad1)") (class "Default")
      (node (ref "C31") (pin "1") (pinfunction "1_1") (pintype "passive"))
      (node (ref "R19") (pin "2") (pinfunction "2_2") (pintype "passive"))
    )
    (net (code "228") (name "Net-(C32-Pad1)") (class "Default")
      (node (ref "C32") (pin "1") (pinfunction "1_1") (pintype "passive"))
      (node (ref "R20") (pin "1") (pinfunction "1_1") (pintype "passive"))
    )
    (net (code "229") (name "Net-(D13-PadA)") (class "Default")
      (node (ref "D13") (pin "A") (pinfunction "A_A") (pintype "passive"))
      (node (ref "JP2") (pin "2") (pintype "passive"))
    )
    (net (code "230") (name "Net-(D17-1)") (class "Default")
      (node (ref "D17") (pin "A") (pinfunction "1_A") (pintype "passive"))
      (node (ref "R67") (pin "2") (pintype "passive"))
    )
    (net (code "231") (name "Net-(D17-2)") (class "Default")
      (node (ref "D17") (pin "K") (pinfunction "2_K") (pintype "passive"))
      (node (ref "U22") (pin "4") (pinfunction "P0_4") (pintype "passive"))
    )
    (net (code "232") (name "Net-(D18-1)") (class "Default")
      (node (ref "D18") (pin "A") (pinfunction "1_A") (pintype "passive"))
      (node (ref "R68") (pin "2") (pintype "passive"))
    )
    (net (code "233") (name "Net-(D18-2)") (class "Default")
      (node (ref "D18") (pin "K") (pinfunction "2_K") (pintype "passive"))
      (node (ref "U22") (pin "5") (pinfunction "P1_5") (pintype "passive"))
    )
    (net (code "234") (name "Net-(D19-1)") (class "Default")
      (node (ref "D19") (pin "A") (pinfunction "1_A") (pintype "passive"))
      (node (ref "R69") (pin "2") (pintype "passive"))
    )
    (net (code "235") (name "Net-(D19-2)") (class "Default")
      (node (ref "D19") (pin "K") (pinfunction "2_K") (pintype "passive"))
      (node (ref "U22") (pin "6") (pinfunction "P2_6") (pintype "passive"))
    )
    (net (code "236") (name "Net-(D20-1)") (class "Default")
      (node (ref "D20") (pin "A") (pinfunction "1_A") (pintype "passive"))
      (node (ref "R70") (pin "2") (pintype "passive"))
    )
    (net (code "237") (name "Net-(D20-2)") (class "Default")
      (node (ref "D20") (pin "K") (pinfunction "2_K") (pintype "passive"))
      (node (ref "U22") (pin "7") (pinfunction "P3_7") (pintype "passive"))
    )
    (net (code "238") (name "Net-(D21-1)") (class "Default")
      (node (ref "D21") (pin "A") (pinfunction "1_A") (pintype "passive"))
      (node (ref "R71") (pin "2") (pintype "passive"))
    )
    (net (code "239") (name "Net-(D21-2)") (class "Default")
      (node (ref "D21") (pin "K") (pinfunction "2_K") (pintype "passive"))
      (node (ref "U22") (pin "9") (pinfunction "P4_9") (pintype "passive"))
    )
    (net (code "240") (name "Net-(D22-1)") (class "Default")
      (node (ref "D22") (pin "A") (pinfunction "1_A") (pintype "passive"))
      (node (ref "R72") (pin "2") (pintype "passive"))
    )
    (net (code "241") (name "Net-(D22-2)") (class "Default")
      (node (ref "D22") (pin "K") (pinfunction "2_K") (pintype "passive"))
      (node (ref "U22") (pin "10") (pinfunction "P5_10") (pintype "passive"))
    )
    (net (code "242") (name "Net-(D23-1)") (class "Default")
      (node (ref "D23") (pin "A") (pinfunction "1_A") (pintype "passive"))
      (node (ref "R73") (pin "2") (pintype "passive"))
    )
    (net (code "243") (name "Net-(D23-2)") (class "Default")
      (node (ref "D23") (pin "K") (pinfunction "2_K") (pintype "passive"))
      (node (ref "U22") (pin "11") (pinfunction "P6_11") (pintype "passive"))
    )
    (net (code "244") (name "Net-(D24-1)") (class "Default")
      (node (ref "D24") (pin "A") (pinfunction "1_A") (pintype "passive"))
      (node (ref "R74") (pin "2") (pintype "passive"))
    )
    (net (code "245") (name "Net-(D24-2)") (class "Default")
      (node (ref "D24") (pin "K") (pinfunction "2_K") (pintype "passive"))
      (node (ref "U22") (pin "12") (pinfunction "P7_12") (pintype "passive"))
    )
    (net (code "246") (name "Net-(D29-PadK)") (class "Default")
      (node (ref "D29") (pin "K") (pinfunction "K_K") (pintype "passive"))
      (node (ref "D30") (pin "K") (pinfunction "K_K") (pintype "passive"))
      (node (ref "R1") (pin "1") (pintype "passive"))
    )
    (net (code "247") (name "Net-(JP3-Pad2)") (class "Default")
      (node (ref "JP3") (pin "2") (pintype "passive"))
      (node (ref "R86") (pin "1") (pinfunction "1_1") (pintype "passive"))
    )
    (net (code "248") (name "Net-(LED1-Pad2)") (class "Default")
      (node (ref "LED1") (pin "2") (pinfunction "2_2") (pintype "passive"))
      (node (ref "R76") (pin "1") (pinfunction "1_1") (pintype "passive"))
    )
    (net (code "249") (name "Net-(LED1-Pad4)") (class "Default")
      (node (ref "LED1") (pin "4") (pinfunction "4_4") (pintype "passive"))
      (node (ref "R77") (pin "1") (pinfunction "1_1") (pintype "passive"))
    )
    (net (code "250") (name "Net-(LED1-Pad6)") (class "Default")
      (node (ref "LED1") (pin "6") (pinfunction "6_6") (pintype "passive"))
      (node (ref "R75") (pin "1") (pinfunction "1_1") (pintype "passive"))
    )
    (net (code "251") (name "Net-(R54-TOP)") (class "Default")
      (node (ref "J5") (pin "11") (pinfunction "11_11") (pintype "passive"))
      (node (ref "R54") (pin "1") (pinfunction "TOP_1") (pintype "passive"))
    )
    (net (code "252") (name "Net-(R79-Pad2)") (class "Default")
      (node (ref "R79") (pin "2") (pinfunction "2_2") (pintype "passive"))
      (node (ref "U26") (pin "3") (pintype "passive"))
    )
    (net (code "253") (name "Net-(R80-Pad2)") (class "Default")
      (node (ref "R80") (pin "2") (pinfunction "2_2") (pintype "passive"))
      (node (ref "U27") (pin "3") (pintype "passive"))
    )
    (net (code "254") (name "Net-(R81-Pad1)") (class "Default")
      (node (ref "R81") (pin "1") (pinfunction "1_1") (pintype "passive"))
      (node (ref "U25") (pin "3") (pintype "passive"))
    )
    (net (code "255") (name "Net-(U1-BGRES)") (class "Default")
      (node (ref "R3") (pin "1") (pinfunction "1_1") (pintype "passive"))
      (node (ref "U1") (pin "1") (pinfunction "BGRES_1") (pintype "passive"))
    )
    (net (code "256") (name "Net-(U1-EECS)") (class "Default")
      (node (ref "R4") (pin "1") (pinfunction "1_1") (pintype "passive"))
      (node (ref "U1") (pin "21") (pinfunction "EECS_21") (pintype "passive"))
    )
    (net (code "257") (name "Net-(U1-X1)") (class "Default")
      (node (ref "C4") (pin "2") (pinfunction "2_2") (pintype "passive"))
      (node (ref "U1") (pin "44") (pinfunction "X1_44") (pintype "passive"))
      (node (ref "Y1") (pin "2") (pinfunction "2_2") (pintype "passive"))
    )
    (net (code "258") (name "Net-(U1-X2)") (class "Default")
      (node (ref "C3") (pin "2") (pinfunction "2_2") (pintype "passive"))
      (node (ref "U1") (pin "43") (pinfunction "X2_43") (pintype "passive"))
      (node (ref "Y1") (pin "1") (pinfunction "1_1") (pintype "passive"))
    )
    (net (code "259") (name "Net-(U4-RXC)") (class "Default")
      (node (ref "R9") (pin "2") (pinfunction "2_2") (pintype "passive"))
      (node (ref "U4") (pin "10") (pinfunction "RXC_10") (pintype "passive"))
    )
    (net (code "260") (name "Net-(U4-TXC)") (class "Default")
      (node (ref "R10") (pin "2") (pinfunction "2_2") (pintype "passive"))
      (node (ref "U4") (pin "15") (pinfunction "TXC_15") (pintype "passive"))
    )
    (net (code "261") (name "Net-(U7-OVERFL)") (class "Default")
      (node (ref "R15") (pin "2") (pinfunction "2_2") (pintype "passive"))
      (node (ref "U7") (pin "9") (pinfunction "OVERFL_9") (pintype "passive"))
    )
    (net (code "262") (name "Net-(U7-QMUTE)") (class "Default")
      (node (ref "R16") (pin "2") (pinfunction "2_2") (pintype "passive"))
      (node (ref "U7") (pin "23") (pinfunction "QMUTE_23") (pintype "passive"))
    )
    (net (code "263") (name "Net-(U7-TEST1)") (class "Default")
      (node (ref "R13") (pin "2") (pinfunction "2_2") (pintype "passive"))
      (node (ref "U7") (pin "20") (pinfunction "TEST1_20") (pintype "passive"))
    )
    (net (code "264") (name "Net-(U7-TEST2)") (class "Default")
      (node (ref "R14") (pin "2") (pinfunction "2_2") (pintype "passive"))
      (node (ref "U7") (pin "21") (pinfunction "TEST2_21") (pintype "passive"))
    )
    (net (code "265") (name "Net-(U7-VINL1)") (class "Default")
      (node (ref "R11") (pin "2") (pinfunction "2_2") (pintype "passive"))
      (node (ref "U7") (pin "2") (pinfunction "VINL1_2") (pintype "passive"))
    )
    (net (code "266") (name "Net-(U7-VINR1)") (class "Default")
      (node (ref "R12") (pin "2") (pinfunction "2_2") (pintype "passive"))
      (node (ref "U7") (pin "4") (pinfunction "VINR1_4") (pintype "passive"))
    )
    (net (code "267") (name "Net-(U7-Vref)") (class "Default")
      (node (ref "C27") (pin "1") (pinfunction "1_1") (pintype "passive"))
      (node (ref "C28") (pin "1") (pinfunction "1_1") (pintype "passive"))
      (node (ref "U7") (pin "28") (pinfunction "Vref_28") (pintype "passive"))
    )
    (net (code "268") (name "Net-(U8A-IN+)") (class "Default")
      (node (ref "R21") (pin "1") (pinfunction "1_1") (pintype "passive"))
      (node (ref "U8") (pin "3") (pinfunction "IN+_3") (pintype "input"))
    )
    (net (code "269") (name "Net-(U8A-IN-)") (class "Default")
      (node (ref "C35") (pin "2") (pinfunction "2_2") (pintype "passive"))
      (node (ref "R17") (pin "1") (pinfunction "1_1") (pintype "passive"))
      (node (ref "R19") (pin "1") (pinfunction "1_1") (pintype "passive"))
      (node (ref "U8") (pin "2") (pinfunction "IN-_2") (pintype "input"))
    )
    (net (code "270") (name "Net-(U8A-OUT)") (class "Default")
      (node (ref "C29") (pin "1") (pinfunction "1_1") (pintype "passive"))
      (node (ref "C35") (pin "1") (pinfunction "1_1") (pintype "passive"))
      (node (ref "R17") (pin "2") (pinfunction "2_2") (pintype "passive"))
      (node (ref "U8") (pin "1") (pinfunction "OUT_1") (pintype "output"))
    )
    (net (code "271") (name "Net-(U8B-IN+)") (class "Default")
      (node (ref "R22") (pin "2") (pinfunction "2_2") (pintype "passive"))
      (node (ref "U8") (pin "5") (pinfunction "IN+_5") (pintype "input"))
    )
    (net (code "272") (name "Net-(U8B-IN-)") (class "Default")
      (node (ref "C36") (pin "2") (pinfunction "2_2") (pintype "passive"))
      (node (ref "R18") (pin "1") (pinfunction "1_1") (pintype "passive"))
      (node (ref "R20") (pin "2") (pinfunction "2_2") (pintype "passive"))
      (node (ref "U8") (pin "6") (pinfunction "IN-_6") (pintype "input"))
    )
    (net (code "273") (name "Net-(U8B-OUT)") (class "Default")
      (node (ref "C30") (pin "1") (pinfunction "1_1") (pintype "passive"))
      (node (ref "C36") (pin "1") (pinfunction "1_1") (pintype "passive"))
      (node (ref "R18") (pin "2") (pinfunction "2_2") (pintype "passive"))
      (node (ref "U8") (pin "7") (pinfunction "OUT_7") (pintype "output"))
    )
    (net (code "274") (name "Net-(U9-A)") (class "Default")
      (node (ref "R25") (pin "1") (pinfunction "1_1") (pintype "passive"))
      (node (ref "U9") (pin "1") (pinfunction "A_1") (pintype "passive"))
    )
    (net (code "275") (name "Net-(U9-K)") (class "Default")
      (node (ref "D1") (pin "A") (pinfunction "A_A") (pintype "passive"))
      (node (ref "U9") (pin "2") (pinfunction "K_2") (pintype "passive"))
    )
    (net (code "276") (name "Net-(U10-A)") (class "Default")
      (node (ref "R26") (pin "1") (pinfunction "1_1") (pintype "passive"))
      (node (ref "U10") (pin "1") (pinfunction "A_1") (pintype "passive"))
    )
    (net (code "277") (name "Net-(U10-K)") (class "Default")
      (node (ref "D2") (pin "A") (pinfunction "A_A") (pintype "passive"))
      (node (ref "U10") (pin "2") (pinfunction "K_2") (pintype "passive"))
    )
    (net (code "278") (name "Net-(U11-A)") (class "Default")
      (node (ref "R27") (pin "1") (pinfunction "1_1") (pintype "passive"))
      (node (ref "U11") (pin "1") (pinfunction "A_1") (pintype "passive"))
    )
    (net (code "279") (name "Net-(U11-K)") (class "Default")
      (node (ref "D3") (pin "A") (pinfunction "A_A") (pintype "passive"))
      (node (ref "U11") (pin "2") (pinfunction "K_2") (pintype "passive"))
    )
    (net (code "280") (name "Net-(U12-A)") (class "Default")
      (node (ref "R28") (pin "1") (pinfunction "1_1") (pintype "passive"))
      (node (ref "U12") (pin "1") (pinfunction "A_1") (pintype "passive"))
    )
    (net (code "281") (name "Net-(U12-K)") (class "Default")
      (node (ref "D4") (pin "A") (pinfunction "A_A") (pintype "passive"))
      (node (ref "U12") (pin "2") (pinfunction "K_2") (pintype "passive"))
    )
    (net (code "282") (name "Net-(U13-A)") (class "Default")
      (node (ref "R29") (pin "1") (pinfunction "1_1") (pintype "passive"))
      (node (ref "U13") (pin "1") (pinfunction "A_1") (pintype "passive"))
    )
    (net (code "283") (name "Net-(U13-K)") (class "Default")
      (node (ref "D5") (pin "A") (pinfunction "A_A") (pintype "passive"))
      (node (ref "U13") (pin "2") (pinfunction "K_2") (pintype "passive"))
    )
    (net (code "284") (name "Net-(U14-A)") (class "Default")
      (node (ref "R30") (pin "1") (pinfunction "1_1") (pintype "passive"))
      (node (ref "U14") (pin "1") (pinfunction "A_1") (pintype "passive"))
    )
    (net (code "285") (name "Net-(U14-K)") (class "Default")
      (node (ref "D6") (pin "A") (pinfunction "A_A") (pintype "passive"))
      (node (ref "U14") (pin "2") (pinfunction "K_2") (pintype "passive"))
    )
    (net (code "286") (name "Net-(U15-A)") (class "Default")
      (node (ref "R31") (pin "1") (pinfunction "1_1") (pintype "passive"))
      (node (ref "U15") (pin "1") (pinfunction "A_1") (pintype "passive"))
    )
    (net (code "287") (name "Net-(U15-K)") (class "Default")
      (node (ref "D7") (pin "A") (pinfunction "A_A") (pintype "passive"))
      (node (ref "U15") (pin "2") (pinfunction "K_2") (pintype "passive"))
    )
    (net (code "288") (name "Net-(U16-A)") (class "Default")
      (node (ref "R32") (pin "1") (pinfunction "1_1") (pintype "passive"))
      (node (ref "U16") (pin "1") (pinfunction "A_1") (pintype "passive"))
    )
    (net (code "289") (name "Net-(U16-K)") (class "Default")
      (node (ref "D8") (pin "A") (pinfunction "A_A") (pintype "passive"))
      (node (ref "U16") (pin "2") (pinfunction "K_2") (pintype "passive"))
    )
    (net (code "290") (name "Net-(U17-A)") (class "Default")
      (node (ref "R33") (pin "1") (pinfunction "1_1") (pintype "passive"))
      (node (ref "U17") (pin "1") (pinfunction "A_1") (pintype "passive"))
    )
    (net (code "291") (name "Net-(U17-K)") (class "Default")
      (node (ref "D9") (pin "A") (pinfunction "A_A") (pintype "passive"))
      (node (ref "U17") (pin "2") (pinfunction "K_2") (pintype "passive"))
    )
    (net (code "292") (name "Net-(U18-A)") (class "Default")
      (node (ref "R34") (pin "1") (pinfunction "1_1") (pintype "passive"))
      (node (ref "U18") (pin "1") (pinfunction "A_1") (pintype "passive"))
    )
    (net (code "293") (name "Net-(U18-K)") (class "Default")
      (node (ref "D10") (pin "A") (pinfunction "A_A") (pintype "passive"))
      (node (ref "U18") (pin "2") (pinfunction "K_2") (pintype "passive"))
    )
    (net (code "294") (name "Net-(U21-MR)") (class "Default")
      (node (ref "C43") (pin "1") (pinfunction "1_1") (pintype "passive"))
      (node (ref "JP2") (pin "1") (pintype "passive"))
      (node (ref "S1") (pin "2") (pinfunction "2_2") (pintype "passive"))
      (node (ref "U21") (pin "1") (pinfunction "MR_1") (pintype "passive"))
    )
    (net (code "295") (name "Net-(U21-PFI)") (class "Default")
      (node (ref "R2") (pin "2") (pinfunction "2_2") (pintype "passive"))
      (node (ref "U21") (pin "4") (pinfunction "PFI_4") (pintype "passive"))
    )
    (net (code "296") (name "Net-(U21-WDO)") (class "Default")
      (node (ref "D13") (pin "K") (pinfunction "K_K") (pintype "passive"))
      (node (ref "U21") (pin "8") (pinfunction "WDO_8") (pintype "passive"))
    )
    (net (code "297") (name "Net-(U23-OUT)") (class "Default")
      (node (ref "D16") (pin "K") (pinfunction "K_K") (pintype "passive"))
      (node (ref "L8") (pin "1") (pinfunction "1_1") (pintype "passive"))
      (node (ref "U23") (pin "2") (pinfunction "OUT_2") (pintype "passive"))
    )
    (net (code "298") (name "Net-(U28-A)") (class "Default")
      (node (ref "R85") (pin "1") (pinfunction "1_1") (pintype "passive"))
      (node (ref "U28") (pin "6") (pinfunction "A_6") (pintype "passive"))
    )
    (net (code "299") (name "Net-(U28-B)") (class "Default")
      (node (ref "R84") (pin "2") (pinfunction "2_2") (pintype "passive"))
      (node (ref "U28") (pin "7") (pinfunction "B_7") (pintype "passive"))
    )
    (net (code "300") (name "Net-(U28-DE)") (class "Default")
      (node (ref "R82") (pin "2") (pinfunction "2_2") (pintype "passive"))
      (node (ref "U26") (pin "6") (pintype "passive"))
      (node (ref "U28") (pin "2") (pinfunction "~{RE}_2") (pintype "passive"))
      (node (ref "U28") (pin "3") (pinfunction "DE_3") (pintype "passive"))
    )
    (net (code "301") (name "Net-(U28-DI)") (class "Default")
      (node (ref "R83") (pin "1") (pinfunction "1_1") (pintype "passive"))
      (node (ref "U27") (pin "6") (pintype "passive"))
      (node (ref "U28") (pin "4") (pinfunction "DI_4") (pintype "passive"))
    )
    (net (code "302") (name "Net-(U28-RO)") (class "Default")
      (node (ref "R81") (pin "2") (pinfunction "2_2") (pintype "passive"))
      (node (ref "U28") (pin "1") (pinfunction "RO_1") (pintype "passive"))
    )
    (net (code "303") (name "VDD5V") (class "Default")
      (node (ref "C50") (pin "1") (pinfunction "1_1") (pintype "passive"))
      (node (ref "C51") (pin "1") (pinfunction "1_1") (pintype "passive"))
      (node (ref "L8") (pin "2") (pinfunction "2_2") (pintype "passive"))
      (node (ref "U23") (pin "4") (pinfunction "FB_4") (pintype "passive"))
      (node (ref "U24") (pin "3") (pinfunction "Vin_3") (pintype "passive"))
      (node (ref "U30") (pin "2") (pinfunction "VIN_2") (pintype "passive"))
    )
    (net (code "304") (name "VDD33V") (class "Default")
      (node (ref "C1") (pin "1") (pinfunction "1_1") (pintype "passive"))
      (node (ref "C12") (pin "1") (pinfunction "1_1") (pintype "passive"))
      (node (ref "C13") (pin "1") (pinfunction "1_1") (pintype "passive"))
      (node (ref "C2") (pin "1") (pinfunction "1_1") (pintype "passive"))
      (node (ref "C23") (pin "2") (pinfunction "2_2") (pintype "passive"))
      (node (ref "C25") (pin "1") (pinfunction "1_1") (pintype "passive"))
      (node (ref "C44") (pin "2") (pinfunction "2_2") (pintype "passive"))
      (node (ref "C45") (pin "1") (pinfunction "1_1") (pintype "passive"))
      (node (ref "C46") (pin "1") (pinfunction "1_1") (pintype "passive"))
      (node (ref "C47") (pin "2") (pinfunction "2_2") (pintype "passive"))
      (node (ref "C54") (pin "1") (pinfunction "1_1") (pintype "passive"))
      (node (ref "C55") (pin "1") (pinfunction "1_1") (pintype "passive"))
      (node (ref "C56") (pin "1") (pinfunction "1_1") (pintype "passive"))
      (node (ref "D29") (pin "A") (pinfunction "A_A") (pintype "passive"))
      (node (ref "J1") (pin "161") (pinfunction "161_161") (pintype "passive"))
      (node (ref "J1") (pin "162") (pinfunction "162_162") (pintype "passive"))
      (node (ref "J3") (pin "4") (pinfunction "VDD_4") (pintype "passive"))
      (node (ref "J4") (pin "1") (pinfunction "1_1") (pintype "passive"))
      (node (ref "J5") (pin "1") (pinfunction "1_1") (pintype "passive"))
      (node (ref "J5") (pin "2") (pinfunction "2_2") (pintype "passive"))
      (node (ref "L1") (pin "1") (pinfunction "1_1") (pintype "passive"))
      (node (ref "L4") (pin "1") (pinfunction "1_1") (pintype "passive"))
      (node (ref "LED1") (pin "1") (pinfunction "1_1") (pintype "passive"))
      (node (ref "LED1") (pin "3") (pinfunction "3_3") (pintype "passive"))
      (node (ref "LED1") (pin "5") (pinfunction "5_5") (pintype "passive"))
      (node (ref "R37") (pin "2") (pinfunction "2_2") (pintype "passive"))
      (node (ref "R38") (pin "2") (pinfunction "2_2") (pintype "passive"))
      (node (ref "R39") (pin "2") (pinfunction "2_2") (pintype "passive"))
      (node (ref "R40") (pin "2") (pinfunction "2_2") (pintype "passive"))
      (node (ref "R41") (pin "2") (pinfunction "2_2") (pintype "passive"))
      (node (ref "R42") (pin "2") (pinfunction "2_2") (pintype "passive"))
      (node (ref "R43") (pin "2") (pinfunction "2_2") (pintype "passive"))
      (node (ref "R44") (pin "2") (pinfunction "2_2") (pintype "passive"))
      (node (ref "R45") (pin "2") (pinfunction "2_2") (pintype "passive"))
      (node (ref "R46") (pin "2") (pinfunction "2_2") (pintype "passive"))
      (node (ref "R49") (pin "1") (pinfunction "TOP_1") (pintype "passive"))
      (node (ref "R50") (pin "1") (pinfunction "TOP_1") (pintype "passive"))
      (node (ref "R51") (pin "1") (pinfunction "TOP_1") (pintype "passive"))
      (node (ref "R52") (pin "1") (pinfunction "TOP_1") (pintype "passive"))
      (node (ref "R55") (pin "1") (pinfunction "TOP_1") (pintype "passive"))
      (node (ref "R56") (pin "1") (pinfunction "TOP_1") (pintype "passive"))
      (node (ref "R57") (pin "1") (pinfunction "TOP_1") (pintype "passive"))
      (node (ref "R58") (pin "1") (pinfunction "TOP_1") (pintype "passive"))
      (node (ref "R59") (pin "1") (pinfunction "TOP_1") (pintype "passive"))
      (node (ref "R60") (pin "1") (pinfunction "TOP_1") (pintype "passive"))
      (node (ref "R61") (pin "1") (pinfunction "TOP_1") (pintype "passive"))
      (node (ref "R62") (pin "1") (pinfunction "TOP_1") (pintype "passive"))
      (node (ref "R65") (pin "1") (pintype "passive"))
      (node (ref "R66") (pin "1") (pintype "passive"))
      (node (ref "R67") (pin "1") (pintype "passive"))
      (node (ref "R68") (pin "1") (pintype "passive"))
      (node (ref "R69") (pin "1") (pintype "passive"))
      (node (ref "R70") (pin "1") (pintype "passive"))
      (node (ref "R71") (pin "1") (pintype "passive"))
      (node (ref "R72") (pin "1") (pintype "passive"))
      (node (ref "R73") (pin "1") (pintype "passive"))
      (node (ref "R74") (pin "1") (pintype "passive"))
      (node (ref "R78") (pin "2") (pinfunction "2_2") (pintype "passive"))
      (node (ref "U21") (pin "2") (pinfunction "VCC_2") (pintype "passive"))
      (node (ref "U22") (pin "16") (pinfunction "VCC_16") (pintype "passive"))
      (node (ref "U24") (pin "2") (pinfunction "Vout_2") (pintype "passive"))
      (node (ref "U24") (pin "4") (pinfunction "Vout_4") (pintype "passive"))
      (node (ref "U25") (pin "8") (pintype "passive"))
      (node (ref "U26") (pin "2") (pintype "passive"))
      (node (ref "U27") (pin "2") (pintype "passive"))
      (node (ref "U7") (pin "10") (pinfunction "DVDD_10") (pintype "passive"))
    )
    (net (code "305") (name "unconnected-(CZ1-PadB20)") (class "Default")
      (node (ref "CZ1") (pin "B20") (pinfunction "B20_B20") (pintype "passive"))
    )
    (net (code "306") (name "unconnected-(CZ1-PadB22)") (class "Default")
      (node (ref "CZ1") (pin "B22") (pinfunction "B22_B22") (pintype "passive"))
    )
    (net (code "307") (name "unconnected-(CZ1-PadB26)") (class "Default")
      (node (ref "CZ1") (pin "B26") (pinfunction "B26_B26") (pintype "passive"))
    )
    (net (code "308") (name "unconnected-(CZ1-PadD22)") (class "Default")
      (node (ref "CZ1") (pin "D22") (pinfunction "D22_D22") (pintype "passive"))
    )
    (net (code "309") (name "unconnected-(CZ1-PadD26)") (class "Default")
      (node (ref "CZ1") (pin "D26") (pinfunction "D26_D26") (pintype "passive"))
    )
    (net (code "310") (name "unconnected-(CZ1-PadZ12)") (class "Default")
      (node (ref "CZ1") (pin "Z12") (pinfunction "Z12_Z12") (pintype "passive"))
    )
    (net (code "311") (name "unconnected-(CZ1-PadZ14)") (class "Default")
      (node (ref "CZ1") (pin "Z14") (pinfunction "Z14_Z14") (pintype "passive"))
    )
    (net (code "312") (name "unconnected-(CZ1-PadZ16)") (class "Default")
      (node (ref "CZ1") (pin "Z16") (pinfunction "Z16_Z16") (pintype "passive"))
    )
    (net (code "313") (name "unconnected-(CZ1-PadZ20)") (class "Default")
      (node (ref "CZ1") (pin "Z20") (pinfunction "Z20_Z20") (pintype "passive"))
    )
    (net (code "314") (name "unconnected-(CZ1-PadZ22)") (class "Default")
      (node (ref "CZ1") (pin "Z22") (pinfunction "Z22_Z22") (pintype "passive"))
    )
    (net (code "315") (name "unconnected-(CZ1-PadZ26)") (class "Default")
      (node (ref "CZ1") (pin "Z26") (pinfunction "Z26_Z26") (pintype "passive"))
    )
    (net (code "316") (name "unconnected-(CZ1-PadZ30)") (class "Default")
      (node (ref "CZ1") (pin "Z30") (pinfunction "Z30_Z30") (pintype "passive"))
    )
    (net (code "317") (name "unconnected-(J1-Pad171)") (class "Default")
      (node (ref "J1") (pin "171") (pinfunction "171_171") (pintype "passive"))
    )
    (net (code "318") (name "unconnected-(J1-Pad172)") (class "Default")
      (node (ref "J1") (pin "172") (pinfunction "172_172") (pintype "passive"))
    )
    (net (code "319") (name "unconnected-(J5-Pad17)") (class "Default")
      (node (ref "J5") (pin "17") (pinfunction "17_17") (pintype "passive"))
    )
    (net (code "320") (name "unconnected-(J5-Pad19)") (class "Default")
      (node (ref "J5") (pin "19") (pinfunction "19_19") (pintype "passive"))
    )
    (net (code "321") (name "unconnected-(U1-EECK-Pad20)") (class "Default")
      (node (ref "U1") (pin "20") (pinfunction "EECK_20") (pintype "passive"))
    )
    (net (code "322") (name "unconnected-(U1-EEDI0-Pad19)") (class "Default")
      (node (ref "U1") (pin "19") (pinfunction "EEDI0_19") (pintype "passive"))
    )
    (net (code "323") (name "unconnected-(U1-SD-Pad46)") (class "Default")
      (node (ref "U1") (pin "46") (pinfunction "SD_46") (pintype "passive"))
    )
    (net (code "324") (name "unconnected-(U7-AGCSTAT-Pad22)") (class "Default")
      (node (ref "U7") (pin "22") (pinfunction "AGCSTAT_22") (pintype "passive"))
    )
    (net (code "325") (name "unconnected-(U7-VINL2-Pad6)") (class "Default")
      (node (ref "U7") (pin "6") (pinfunction "VINL2_6") (pintype "passive"))
    )
    (net (code "326") (name "unconnected-(U7-VINR3-Pad8)") (class "Default")
      (node (ref "U7") (pin "8") (pinfunction "VINR3_8") (pintype "passive"))
    )
    (net (code "327") (name "unconnected-(U7-VOUTL-Pad26)") (class "Default")
      (node (ref "U7") (pin "26") (pinfunction "VOUTL_26") (pintype "passive"))
    )
    (net (code "328") (name "unconnected-(U7-VOUTR-Pad24)") (class "Default")
      (node (ref "U7") (pin "24") (pinfunction "VOUTR_24") (pintype "passive"))
    )
    (net (code "329") (name "unconnected-(U8B-V+-Pad8)") (class "Default")
      (node (ref "U8") (pin "8") (pinfunction "V+_8") (pintype "power_in"))
    )
    (net (code "330") (name "unconnected-(U8B-V--Pad4)") (class "Default")
      (node (ref "U8") (pin "4") (pinfunction "V-_4") (pintype "power_in"))
    )
    (net (code "331") (name "unconnected-(U21-PFO-Pad5)") (class "Default")
      (node (ref "U21") (pin "5") (pinfunction "PFO_5") (pintype "passive"))
    )
    (net (code "332") (name "unconnected-(U22-{slash}INT-Pad13)") (class "Default")
      (node (ref "U22") (pin "13") (pinfunction "/INT_13") (pintype "passive"))
    )
    (net (code "333") (name "unconnected-(U25-Pad4)") (class "Default")
      (node (ref "U25") (pin "4") (pintype "passive"))
    )
    (net (code "334") (name "unconnected-(U25-Pad7)") (class "Default")
      (node (ref "U25") (pin "7") (pintype "passive"))
    )
    (net (code "335") (name "unconnected-(U26-Pad1)") (class "Default")
      (node (ref "U26") (pin "1") (pintype "passive"))
    )
    (net (code "336") (name "unconnected-(U26-Pad4)") (class "Default")
      (node (ref "U26") (pin "4") (pintype "passive"))
    )
    (net (code "337") (name "unconnected-(U27-Pad1)") (class "Default")
      (node (ref "U27") (pin "1") (pintype "passive"))
    )
    (net (code "338") (name "unconnected-(U27-Pad4)") (class "Default")
      (node (ref "U27") (pin "4") (pintype "passive"))
    )
    (net (code "339") (name "unconnected-(U29-NC-Pad2)") (class "Default")
      (node (ref "U29") (pin "2") (pinfunction "NC_2") (pintype "passive"))
    )
    (net (code "340") (name "unconnected-(U29-NC-Pad3)") (class "Default")
      (node (ref "U29") (pin "3") (pinfunction "NC_3") (pintype "passive"))
    )
    (net (code "341") (name "unconnected-(U29-NC-Pad5)") (class "Default")
      (node (ref "U29") (pin "5") (pinfunction "NC_5") (pintype "passive"))
    )
    (net (code "342") (name "unconnected-(U29-NC-Pad7)") (class "Default")
      (node (ref "U29") (pin "7") (pinfunction "NC_7") (pintype "passive"))
    )
    (net (code "343") (name "unconnected-(U29-NC-Pad8)") (class "Default")
      (node (ref "U29") (pin "8") (pinfunction "NC_8") (pintype "passive"))
    )
  )
)
